# IRC2K16.net
KiCad netlist of a schematic drawn in EAGLE
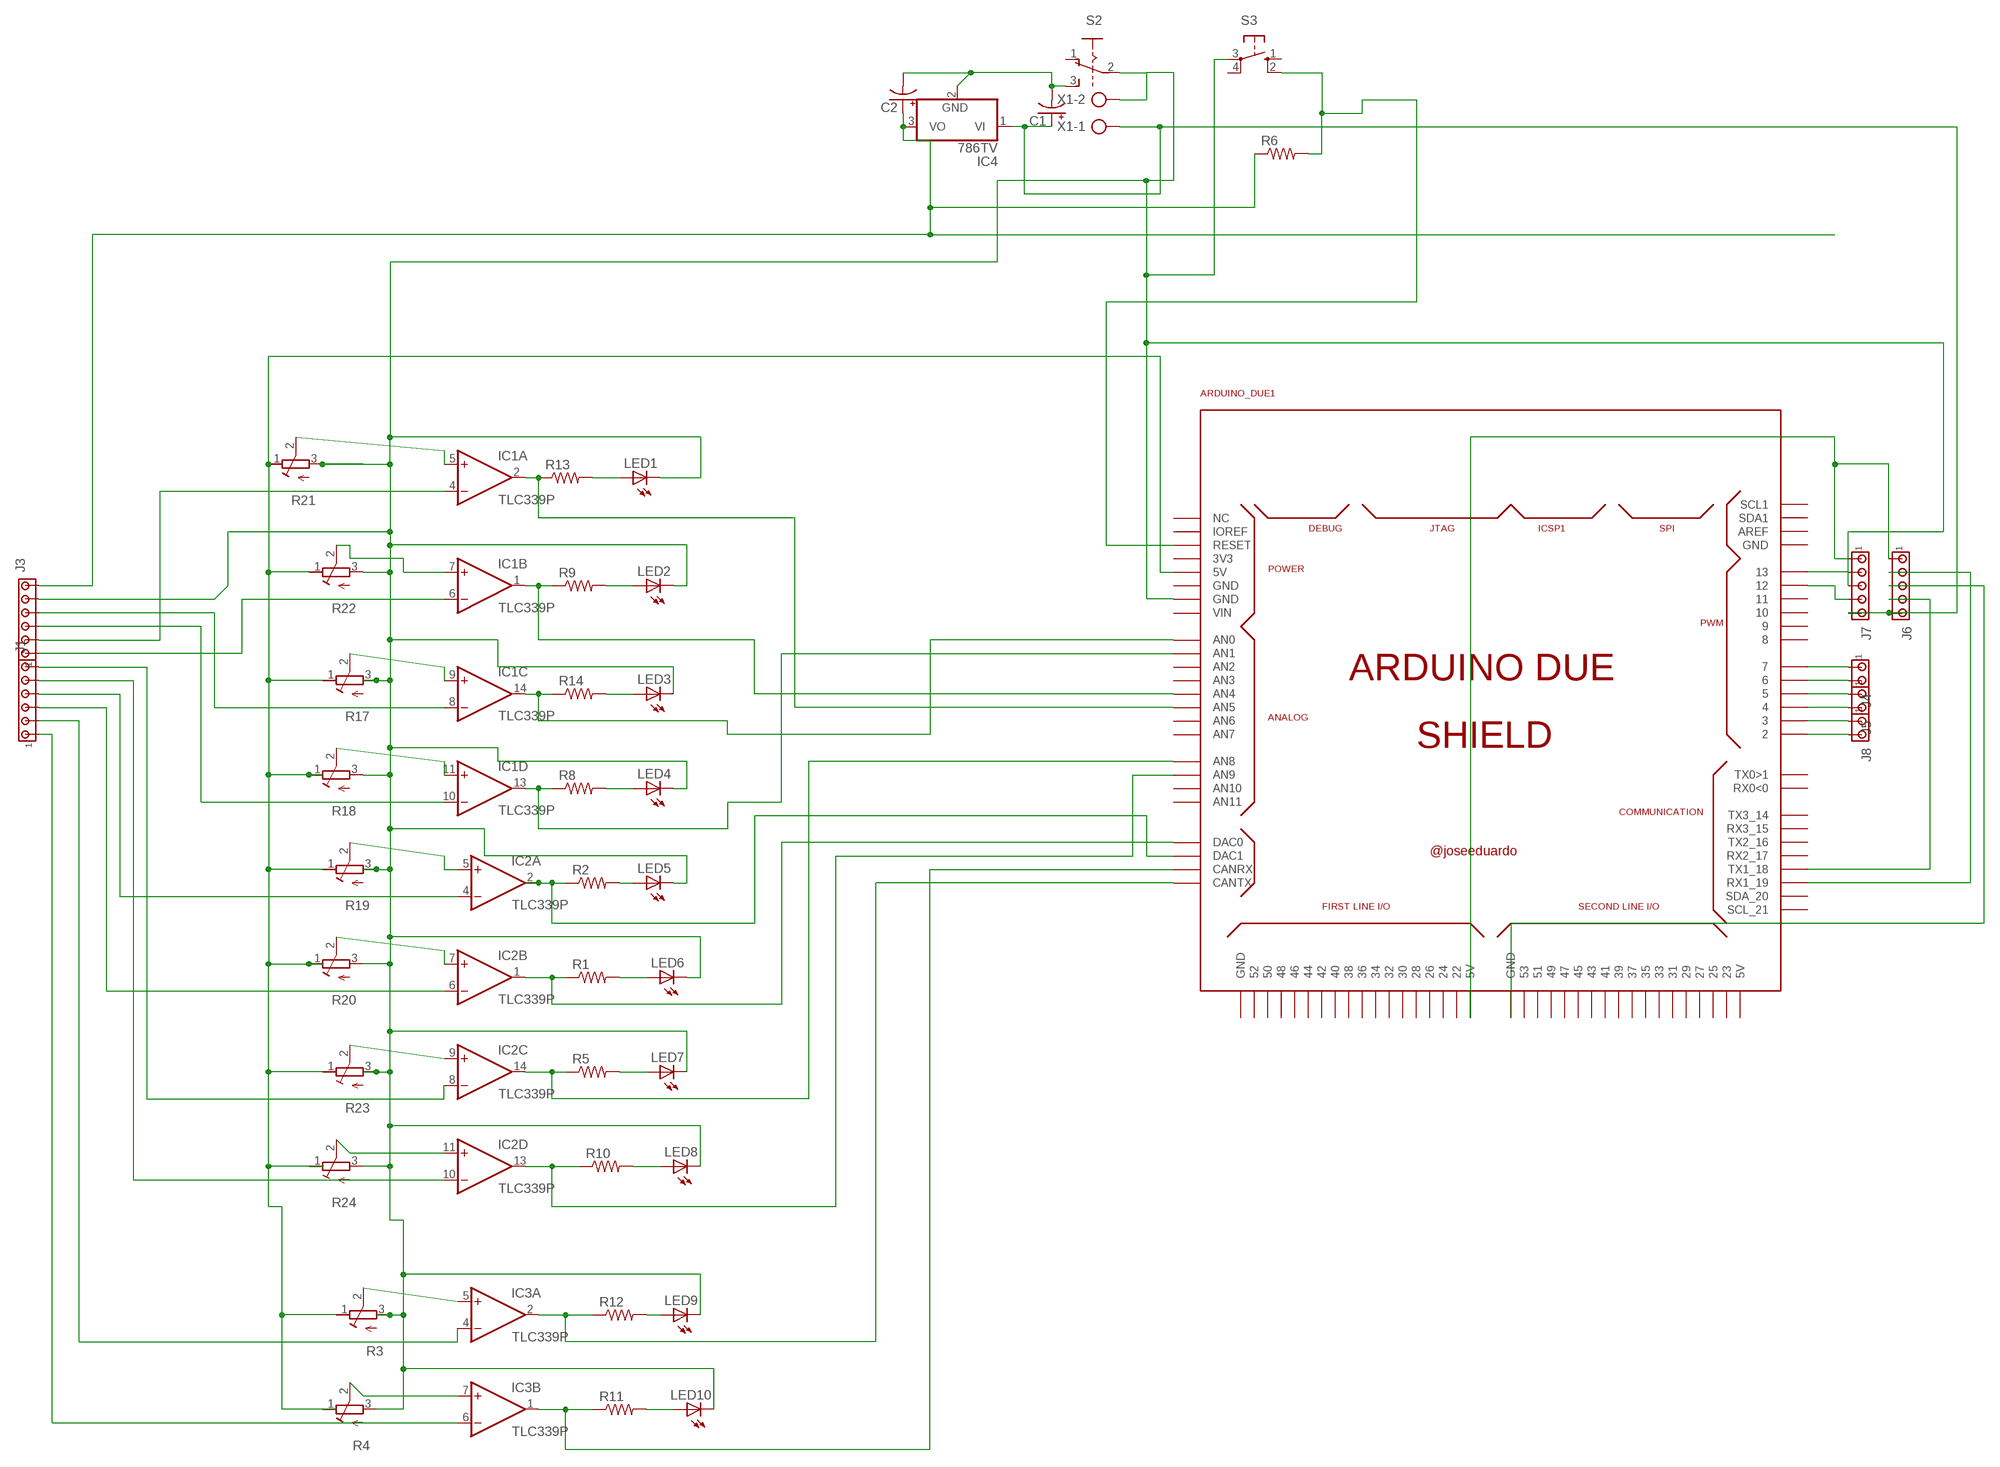
[diagram p0: schematic, sheet 1]
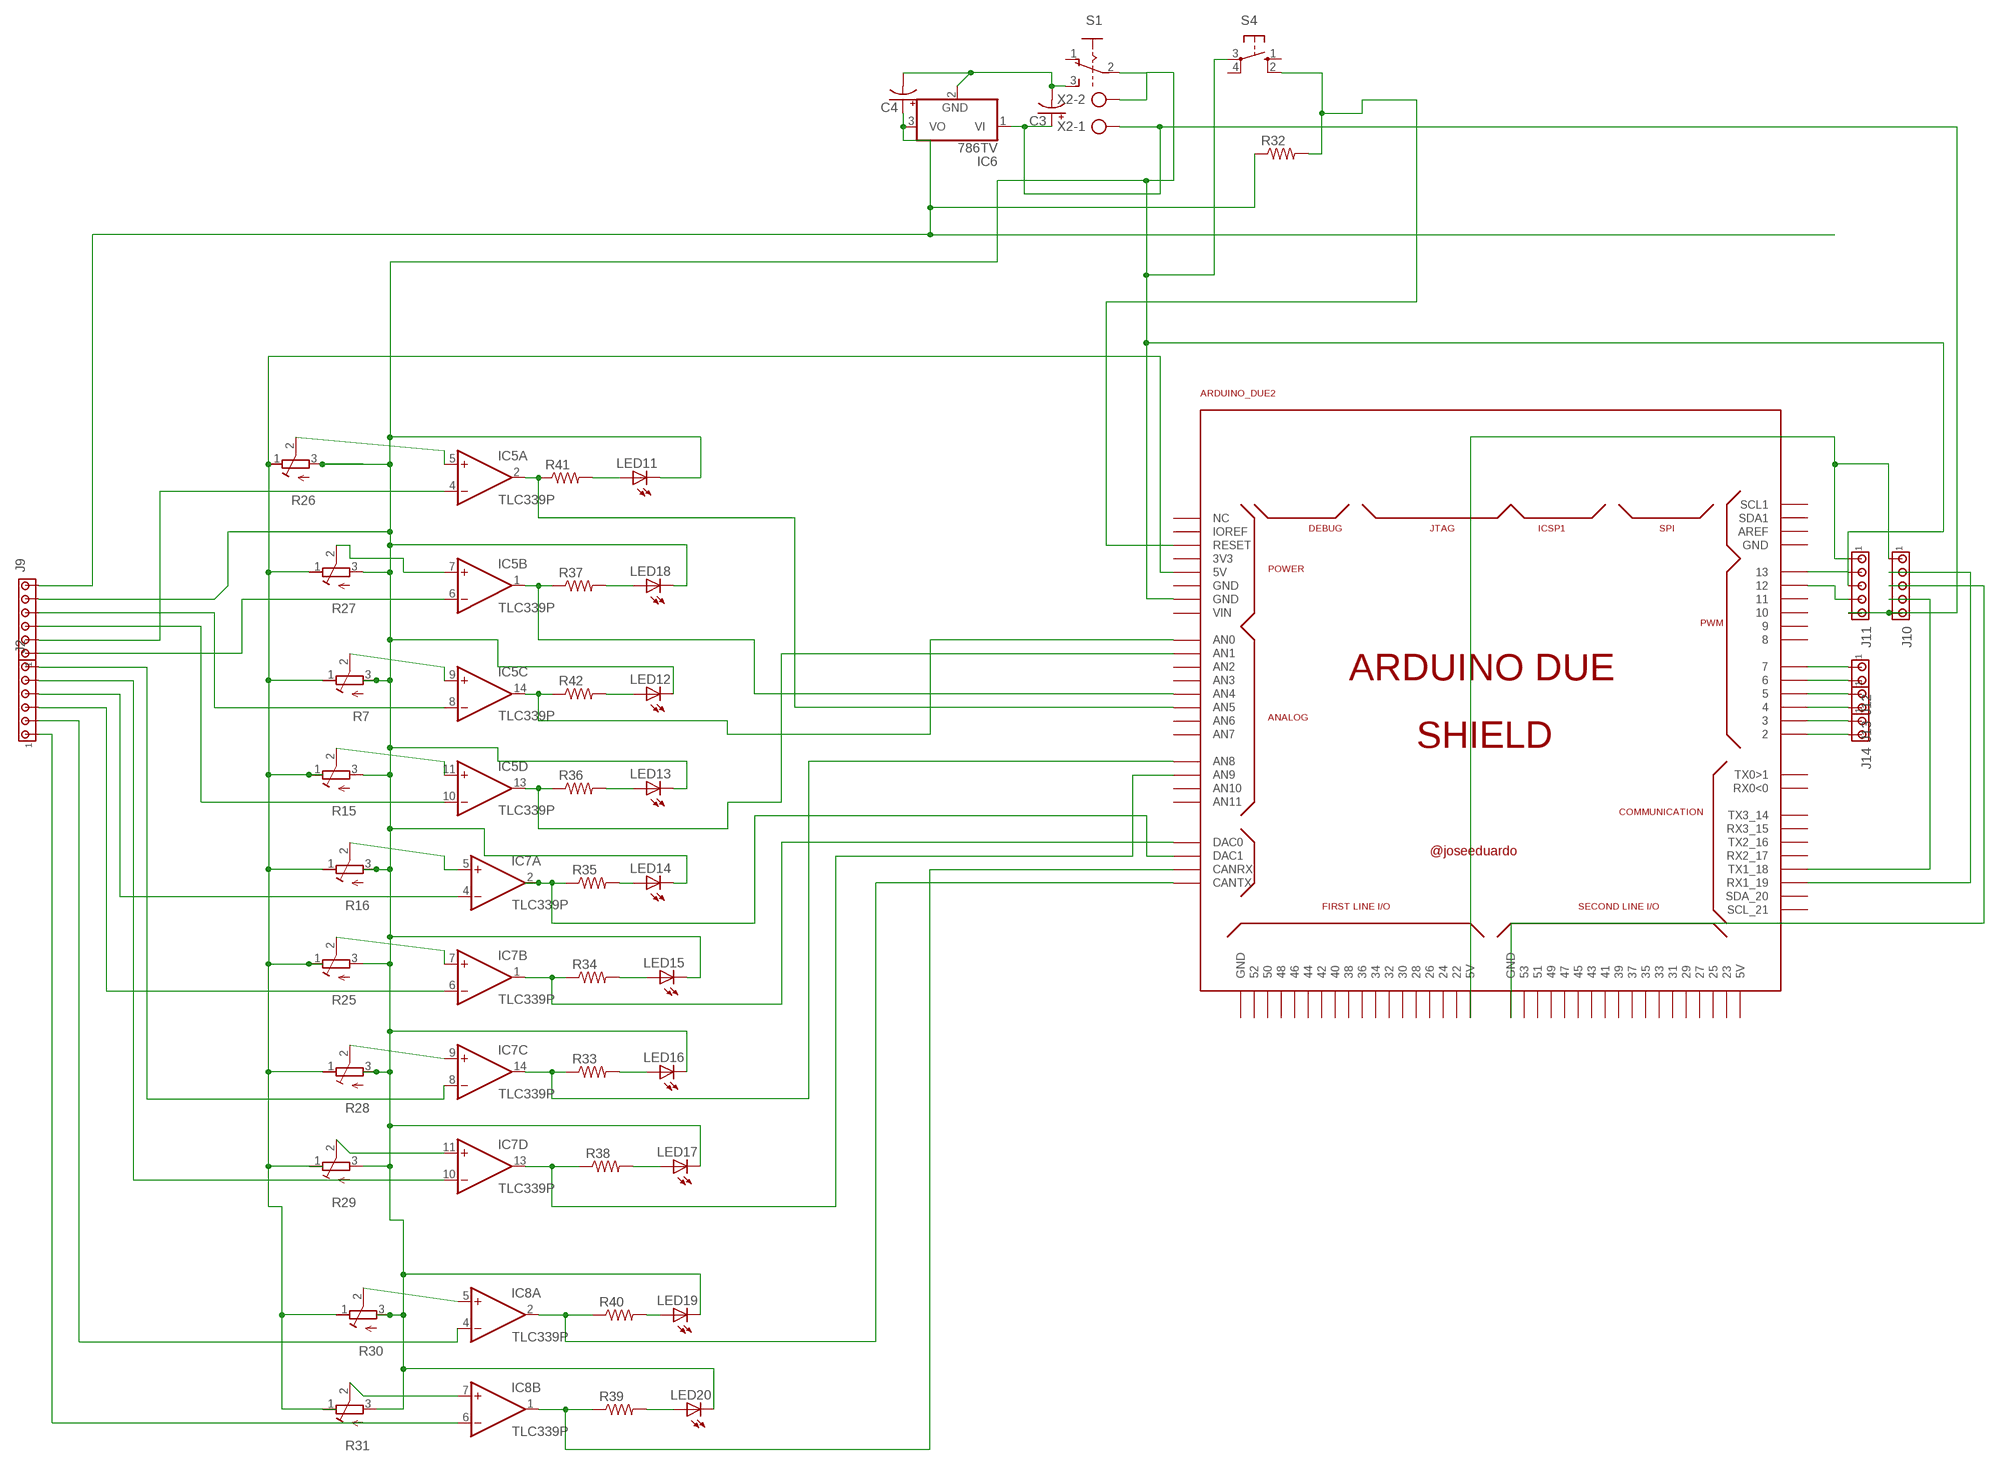
[diagram p1: schematic, sheet 2]

(export (version "E")
  (design (tool "Eeschema 10.0.6"))
  (components
    (comp (ref "ARDUINO_DUE1")
      (value "ARDUINO_DUE_SHIELD")
      (footprint "eagle-import:ARDUINO_DUE_SHIELD")
      (libsource (lib "eagle-import") (part "ARDUINO_DUE_SHIELD"))
    )
    (comp (ref "C1")
      (value "CPOL-USE5-10.5")
      (footprint "eagle-import:E5-10,5")
      (libsource (lib "eagle-import") (part "CPOL-USE5-10.5"))
    )
    (comp (ref "C2")
      (value "CPOL-USE5-10.5")
      (footprint "eagle-import:E5-10,5")
      (libsource (lib "eagle-import") (part "CPOL-USE5-10.5"))
    )
    (comp (ref "IC1")
      (value "TLC339P")
      (footprint "eagle-import:DIL14")
      (libsource (lib "eagle-import") (part "TLC339P"))
    )
    (comp (ref "IC2")
      (value "TLC339P")
      (footprint "eagle-import:DIL14")
      (libsource (lib "eagle-import") (part "TLC339P"))
    )
    (comp (ref "IC3")
      (value "TLC339P")
      (footprint "eagle-import:DIL14")
      (libsource (lib "eagle-import") (part "TLC339P"))
    )
    (comp (ref "IC4")
      (value "786TV")
      (footprint "eagle-import:TO220V")
      (libsource (lib "eagle-import") (part "78TV6"))
    )
    (comp (ref "J1")
      (value "MTA06-100")
      (footprint "eagle-import:10X06MTA")
      (libsource (lib "eagle-import") (part "MTA06-100"))
    )
    (comp (ref "J3")
      (value "MTA06-100")
      (footprint "eagle-import:10X06MTA")
      (libsource (lib "eagle-import") (part "MTA06-100"))
    )
    (comp (ref "J4")
      (value "MTA02-100")
      (footprint "eagle-import:10X02MTA")
      (libsource (lib "eagle-import") (part "MTA02-100"))
    )
    (comp (ref "J5")
      (value "MTA02-100")
      (footprint "eagle-import:10X02MTA")
      (libsource (lib "eagle-import") (part "MTA02-100"))
    )
    (comp (ref "J6")
      (value "MTA05-100")
      (footprint "eagle-import:10X05MTA")
      (libsource (lib "eagle-import") (part "MTA05-100"))
    )
    (comp (ref "J7")
      (value "MTA05-100")
      (footprint "eagle-import:10X05MTA")
      (libsource (lib "eagle-import") (part "MTA05-100"))
    )
    (comp (ref "J8")
      (value "MTA02-100")
      (footprint "eagle-import:10X02MTA")
      (libsource (lib "eagle-import") (part "MTA02-100"))
    )
    (comp (ref "LED1")
      (value "LED3MM")
      (footprint "eagle-import:LED3MM")
      (libsource (lib "eagle-import") (part "LED3MM"))
    )
    (comp (ref "LED2")
      (value "LED3MM")
      (footprint "eagle-import:LED3MM")
      (libsource (lib "eagle-import") (part "LED3MM"))
    )
    (comp (ref "LED3")
      (value "LED3MM")
      (footprint "eagle-import:LED3MM")
      (libsource (lib "eagle-import") (part "LED3MM"))
    )
    (comp (ref "LED4")
      (value "LED3MM")
      (footprint "eagle-import:LED3MM")
      (libsource (lib "eagle-import") (part "LED3MM"))
    )
    (comp (ref "LED5")
      (value "LED3MM")
      (footprint "eagle-import:LED3MM")
      (libsource (lib "eagle-import") (part "LED3MM"))
    )
    (comp (ref "LED6")
      (value "LED3MM")
      (footprint "eagle-import:LED3MM")
      (libsource (lib "eagle-import") (part "LED3MM"))
    )
    (comp (ref "LED7")
      (value "LED3MM")
      (footprint "eagle-import:LED3MM")
      (libsource (lib "eagle-import") (part "LED3MM"))
    )
    (comp (ref "LED8")
      (value "LED3MM")
      (footprint "eagle-import:LED3MM")
      (libsource (lib "eagle-import") (part "LED3MM"))
    )
    (comp (ref "LED9")
      (value "LED3MM")
      (footprint "eagle-import:LED3MM")
      (libsource (lib "eagle-import") (part "LED3MM"))
    )
    (comp (ref "LED10")
      (value "LED3MM")
      (footprint "eagle-import:LED3MM")
      (libsource (lib "eagle-import") (part "LED3MM"))
    )
    (comp (ref "R1")
      (value "R-US_0411/3V")
      (footprint "eagle-import:0411V")
      (libsource (lib "eagle-import") (part "resistor_R-US_0411/3V"))
    )
    (comp (ref "R2")
      (value "R-US_0411/3V")
      (footprint "eagle-import:0411V")
      (libsource (lib "eagle-import") (part "resistor_R-US_0411/3V"))
    )
    (comp (ref "R3")
      (value "R-TRIMMT93YA")
      (footprint "eagle-import:RTRIMT93YA")
      (libsource (lib "eagle-import") (part "R-TRIMMT93YA"))
    )
    (comp (ref "R4")
      (value "R-TRIMMT93YA")
      (footprint "eagle-import:RTRIMT93YA")
      (libsource (lib "eagle-import") (part "R-TRIMMT93YA"))
    )
    (comp (ref "R5")
      (value "R-US_0411/3V")
      (footprint "eagle-import:0411V")
      (libsource (lib "eagle-import") (part "resistor_R-US_0411/3V"))
    )
    (comp (ref "R6")
      (value "R-US_0207/10")
      (footprint "eagle-import:0207_10")
      (libsource (lib "eagle-import") (part "R-US_0207/10"))
    )
    (comp (ref "R8")
      (value "R-US_0411/3V")
      (footprint "eagle-import:0411V")
      (libsource (lib "eagle-import") (part "resistor_R-US_0411/3V"))
    )
    (comp (ref "R9")
      (value "R-US_0411/3V")
      (footprint "eagle-import:0411V")
      (libsource (lib "eagle-import") (part "resistor_R-US_0411/3V"))
    )
    (comp (ref "R10")
      (value "R-US_0411/3V")
      (footprint "eagle-import:0411V")
      (libsource (lib "eagle-import") (part "resistor_R-US_0411/3V"))
    )
    (comp (ref "R11")
      (value "R-US_0411/3V")
      (footprint "eagle-import:0411V")
      (libsource (lib "eagle-import") (part "resistor_R-US_0411/3V"))
    )
    (comp (ref "R12")
      (value "R-US_0411/3V")
      (footprint "eagle-import:0411V")
      (libsource (lib "eagle-import") (part "resistor_R-US_0411/3V"))
    )
    (comp (ref "R13")
      (value "R-US_0411/3V")
      (footprint "eagle-import:0411V")
      (libsource (lib "eagle-import") (part "resistor_R-US_0411/3V"))
    )
    (comp (ref "R14")
      (value "R-US_0411/3V")
      (footprint "eagle-import:0411V")
      (libsource (lib "eagle-import") (part "resistor_R-US_0411/3V"))
    )
    (comp (ref "R17")
      (value "R-TRIMMT93YA")
      (footprint "eagle-import:RTRIMT93YA")
      (libsource (lib "eagle-import") (part "R-TRIMMT93YA"))
    )
    (comp (ref "R18")
      (value "R-TRIMMT93YA")
      (footprint "eagle-import:RTRIMT93YA")
      (libsource (lib "eagle-import") (part "R-TRIMMT93YA"))
    )
    (comp (ref "R19")
      (value "R-TRIMMT93YA")
      (footprint "eagle-import:RTRIMT93YA")
      (libsource (lib "eagle-import") (part "R-TRIMMT93YA"))
    )
    (comp (ref "R20")
      (value "R-TRIMMT93YA")
      (footprint "eagle-import:RTRIMT93YA")
      (libsource (lib "eagle-import") (part "R-TRIMMT93YA"))
    )
    (comp (ref "R21")
      (value "R-TRIMMT93YA")
      (footprint "eagle-import:RTRIMT93YA")
      (libsource (lib "eagle-import") (part "R-TRIMMT93YA"))
    )
    (comp (ref "R22")
      (value "R-TRIMMT93YA")
      (footprint "eagle-import:RTRIMT93YA")
      (libsource (lib "eagle-import") (part "R-TRIMMT93YA"))
    )
    (comp (ref "R23")
      (value "R-TRIMMT93YA")
      (footprint "eagle-import:RTRIMT93YA")
      (libsource (lib "eagle-import") (part "R-TRIMMT93YA"))
    )
    (comp (ref "R24")
      (value "R-TRIMMT93YA")
      (footprint "eagle-import:RTRIMT93YA")
      (libsource (lib "eagle-import") (part "R-TRIMMT93YA"))
    )
    (comp (ref "S2")
      (value "A68-A31")
      (footprint "eagle-import:A68-A31")
      (libsource (lib "eagle-import") (part "A68-A31"))
    )
    (comp (ref "S3")
      (value "10-XX")
      (footprint "eagle-import:B3F-10XX")
      (fields (field (name "MPN") "B3F-1000"))
      (libsource (lib "eagle-import") (part "10-XX"))
    )
    (comp (ref "X1")
      (value "AK300/2")
      (footprint "eagle-import:AK300_2")
      (libsource (lib "eagle-import") (part "AK300/2"))
    )
    (comp (ref "ARDUINO_DUE2")
      (value "ARDUINO_DUE_SHIELD")
      (footprint "eagle-import:ARDUINO_DUE_SHIELD")
      (libsource (lib "eagle-import") (part "ARDUINO_DUE_SHIELD"))
    )
    (comp (ref "C3")
      (value "CPOL-USE5-10.5")
      (footprint "eagle-import:E5-10,5")
      (libsource (lib "eagle-import") (part "CPOL-USE5-10.5"))
    )
    (comp (ref "C4")
      (value "CPOL-USE5-10.5")
      (footprint "eagle-import:E5-10,5")
      (libsource (lib "eagle-import") (part "CPOL-USE5-10.5"))
    )
    (comp (ref "IC5")
      (value "TLC339P")
      (footprint "eagle-import:DIL14")
      (libsource (lib "eagle-import") (part "TLC339P"))
    )
    (comp (ref "IC6")
      (value "786TV")
      (footprint "eagle-import:TO220V")
      (libsource (lib "eagle-import") (part "78TV6"))
    )
    (comp (ref "IC7")
      (value "TLC339P")
      (footprint "eagle-import:DIL14")
      (libsource (lib "eagle-import") (part "TLC339P"))
    )
    (comp (ref "IC8")
      (value "TLC339P")
      (footprint "eagle-import:DIL14")
      (libsource (lib "eagle-import") (part "TLC339P"))
    )
    (comp (ref "J2")
      (value "MTA06-100")
      (footprint "eagle-import:10X06MTA")
      (libsource (lib "eagle-import") (part "MTA06-100"))
    )
    (comp (ref "J9")
      (value "MTA06-100")
      (footprint "eagle-import:10X06MTA")
      (libsource (lib "eagle-import") (part "MTA06-100"))
    )
    (comp (ref "J10")
      (value "MTA05-100")
      (footprint "eagle-import:10X05MTA")
      (libsource (lib "eagle-import") (part "MTA05-100"))
    )
    (comp (ref "J11")
      (value "MTA05-100")
      (footprint "eagle-import:10X05MTA")
      (libsource (lib "eagle-import") (part "MTA05-100"))
    )
    (comp (ref "J12")
      (value "MTA02-100")
      (footprint "eagle-import:10X02MTA")
      (libsource (lib "eagle-import") (part "MTA02-100"))
    )
    (comp (ref "J13")
      (value "MTA02-100")
      (footprint "eagle-import:10X02MTA")
      (libsource (lib "eagle-import") (part "MTA02-100"))
    )
    (comp (ref "J14")
      (value "MTA02-100")
      (footprint "eagle-import:10X02MTA")
      (libsource (lib "eagle-import") (part "MTA02-100"))
    )
    (comp (ref "LED11")
      (value "LED3MM")
      (footprint "eagle-import:LED3MM")
      (libsource (lib "eagle-import") (part "LED3MM"))
    )
    (comp (ref "LED12")
      (value "LED3MM")
      (footprint "eagle-import:LED3MM")
      (libsource (lib "eagle-import") (part "LED3MM"))
    )
    (comp (ref "LED13")
      (value "LED3MM")
      (footprint "eagle-import:LED3MM")
      (libsource (lib "eagle-import") (part "LED3MM"))
    )
    (comp (ref "LED14")
      (value "LED3MM")
      (footprint "eagle-import:LED3MM")
      (libsource (lib "eagle-import") (part "LED3MM"))
    )
    (comp (ref "LED15")
      (value "LED3MM")
      (footprint "eagle-import:LED3MM")
      (libsource (lib "eagle-import") (part "LED3MM"))
    )
    (comp (ref "LED16")
      (value "LED3MM")
      (footprint "eagle-import:LED3MM")
      (libsource (lib "eagle-import") (part "LED3MM"))
    )
    (comp (ref "LED17")
      (value "LED3MM")
      (footprint "eagle-import:LED3MM")
      (libsource (lib "eagle-import") (part "LED3MM"))
    )
    (comp (ref "LED18")
      (value "LED3MM")
      (footprint "eagle-import:LED3MM")
      (libsource (lib "eagle-import") (part "LED3MM"))
    )
    (comp (ref "LED19")
      (value "LED3MM")
      (footprint "eagle-import:LED3MM")
      (libsource (lib "eagle-import") (part "LED3MM"))
    )
    (comp (ref "LED20")
      (value "LED3MM")
      (footprint "eagle-import:LED3MM")
      (libsource (lib "eagle-import") (part "LED3MM"))
    )
    (comp (ref "R7")
      (value "R-TRIMMT93YA")
      (footprint "eagle-import:RTRIMT93YA")
      (libsource (lib "eagle-import") (part "R-TRIMMT93YA"))
    )
    (comp (ref "R15")
      (value "R-TRIMMT93YA")
      (footprint "eagle-import:RTRIMT93YA")
      (libsource (lib "eagle-import") (part "R-TRIMMT93YA"))
    )
    (comp (ref "R16")
      (value "R-TRIMMT93YA")
      (footprint "eagle-import:RTRIMT93YA")
      (libsource (lib "eagle-import") (part "R-TRIMMT93YA"))
    )
    (comp (ref "R25")
      (value "R-TRIMMT93YA")
      (footprint "eagle-import:RTRIMT93YA")
      (libsource (lib "eagle-import") (part "R-TRIMMT93YA"))
    )
    (comp (ref "R26")
      (value "R-TRIMMT93YA")
      (footprint "eagle-import:RTRIMT93YA")
      (libsource (lib "eagle-import") (part "R-TRIMMT93YA"))
    )
    (comp (ref "R27")
      (value "R-TRIMMT93YA")
      (footprint "eagle-import:RTRIMT93YA")
      (libsource (lib "eagle-import") (part "R-TRIMMT93YA"))
    )
    (comp (ref "R28")
      (value "R-TRIMMT93YA")
      (footprint "eagle-import:RTRIMT93YA")
      (libsource (lib "eagle-import") (part "R-TRIMMT93YA"))
    )
    (comp (ref "R29")
      (value "R-TRIMMT93YA")
      (footprint "eagle-import:RTRIMT93YA")
      (libsource (lib "eagle-import") (part "R-TRIMMT93YA"))
    )
    (comp (ref "R30")
      (value "R-TRIMMT93YA")
      (footprint "eagle-import:RTRIMT93YA")
      (libsource (lib "eagle-import") (part "R-TRIMMT93YA"))
    )
    (comp (ref "R31")
      (value "R-TRIMMT93YA")
      (footprint "eagle-import:RTRIMT93YA")
      (libsource (lib "eagle-import") (part "R-TRIMMT93YA"))
    )
    (comp (ref "R32")
      (value "R-US_0207/10")
      (footprint "eagle-import:0207_10")
      (libsource (lib "eagle-import") (part "R-US_0207/10"))
    )
    (comp (ref "R33")
      (value "R-US_0411/3V")
      (footprint "eagle-import:0411V")
      (libsource (lib "eagle-import") (part "resistor_R-US_0411/3V"))
    )
    (comp (ref "R34")
      (value "R-US_0411/3V")
      (footprint "eagle-import:0411V")
      (libsource (lib "eagle-import") (part "resistor_R-US_0411/3V"))
    )
    (comp (ref "R35")
      (value "R-US_0411/3V")
      (footprint "eagle-import:0411V")
      (libsource (lib "eagle-import") (part "resistor_R-US_0411/3V"))
    )
    (comp (ref "R36")
      (value "R-US_0411/3V")
      (footprint "eagle-import:0411V")
      (libsource (lib "eagle-import") (part "resistor_R-US_0411/3V"))
    )
    (comp (ref "R37")
      (value "R-US_0411/3V")
      (footprint "eagle-import:0411V")
      (libsource (lib "eagle-import") (part "resistor_R-US_0411/3V"))
    )
    (comp (ref "R38")
      (value "R-US_0411/3V")
      (footprint "eagle-import:0411V")
      (libsource (lib "eagle-import") (part "resistor_R-US_0411/3V"))
    )
    (comp (ref "R39")
      (value "R-US_0411/3V")
      (footprint "eagle-import:0411V")
      (libsource (lib "eagle-import") (part "resistor_R-US_0411/3V"))
    )
    (comp (ref "R40")
      (value "R-US_0411/3V")
      (footprint "eagle-import:0411V")
      (libsource (lib "eagle-import") (part "resistor_R-US_0411/3V"))
    )
    (comp (ref "R41")
      (value "R-US_0411/3V")
      (footprint "eagle-import:0411V")
      (libsource (lib "eagle-import") (part "resistor_R-US_0411/3V"))
    )
    (comp (ref "R42")
      (value "R-US_0411/3V")
      (footprint "eagle-import:0411V")
      (libsource (lib "eagle-import") (part "resistor_R-US_0411/3V"))
    )
    (comp (ref "S1")
      (value "A68-A31")
      (footprint "eagle-import:A68-A31")
      (libsource (lib "eagle-import") (part "A68-A31"))
    )
    (comp (ref "S4")
      (value "10-XX")
      (footprint "eagle-import:B3F-10XX")
      (fields (field (name "MPN") "B3F-1000"))
      (libsource (lib "eagle-import") (part "10-XX"))
    )
    (comp (ref "X2")
      (value "AK300/2")
      (footprint "eagle-import:AK300_2")
      (libsource (lib "eagle-import") (part "AK300/2"))
    )
  )
  (nets
    (net (code "1") (name "Net-(ARDUINO_DUE1-5V-Pad5V0_1)") (class "Default")
      (node (ref "ARDUINO_DUE1") (pin "5V0_1") (pinfunction "5V_5V0_1") (pintype "bidirectional"))
      (node (ref "J6") (pin "1") (pinfunction "1_1") (pintype "passive"))
      (node (ref "J7") (pin "1") (pinfunction "1_1") (pintype "passive"))
    )
    (net (code "2") (name "Net-(ARDUINO_DUE1-AN0)") (class "Default")
      (node (ref "ARDUINO_DUE1") (pin "A0") (pinfunction "AN0_A0") (pintype "bidirectional"))
      (node (ref "IC1") (pin "14") (pinfunction "OUT_14") (pintype "output"))
      (node (ref "R14") (pin "1") (pinfunction "1_1") (pintype "passive"))
    )
    (net (code "3") (name "Net-(ARDUINO_DUE1-AN1)") (class "Default")
      (node (ref "ARDUINO_DUE1") (pin "A1") (pinfunction "AN1_A1") (pintype "bidirectional"))
      (node (ref "IC1") (pin "13") (pinfunction "OUT_13") (pintype "output"))
      (node (ref "R8") (pin "1") (pinfunction "1_1") (pintype "passive"))
    )
    (net (code "4") (name "Net-(ARDUINO_DUE1-AN4)") (class "Default")
      (node (ref "ARDUINO_DUE1") (pin "A4") (pinfunction "AN4_A4") (pintype "bidirectional"))
      (node (ref "IC1") (pin "1") (pinfunction "OUT_1") (pintype "output"))
      (node (ref "R9") (pin "1") (pinfunction "1_1") (pintype "passive"))
    )
    (net (code "5") (name "Net-(ARDUINO_DUE1-AN5)") (class "Default")
      (node (ref "ARDUINO_DUE1") (pin "A5") (pinfunction "AN5_A5") (pintype "bidirectional"))
      (node (ref "IC1") (pin "2") (pinfunction "OUT_2") (pintype "output"))
      (node (ref "R13") (pin "1") (pinfunction "1_1") (pintype "passive"))
    )
    (net (code "6") (name "Net-(ARDUINO_DUE1-AN8)") (class "Default")
      (node (ref "ARDUINO_DUE1") (pin "A8") (pinfunction "AN8_A8") (pintype "bidirectional"))
      (node (ref "IC2") (pin "14") (pinfunction "OUT_14") (pintype "output"))
      (node (ref "R5") (pin "1") (pinfunction "1_1") (pintype "passive"))
    )
    (net (code "7") (name "Net-(ARDUINO_DUE1-AN9)") (class "Default")
      (node (ref "ARDUINO_DUE1") (pin "A9") (pinfunction "AN9_A9") (pintype "bidirectional"))
      (node (ref "IC2") (pin "13") (pinfunction "OUT_13") (pintype "output"))
      (node (ref "R10") (pin "1") (pinfunction "1_1") (pintype "passive"))
    )
    (net (code "8") (name "Net-(ARDUINO_DUE1-GND-PadGND_3)") (class "Default")
      (node (ref "ARDUINO_DUE1") (pin "GND_3") (pinfunction "GND_GND_3") (pintype "bidirectional"))
      (node (ref "J6") (pin "3") (pinfunction "3_3") (pintype "passive"))
    )
    (net (code "9") (name "Net-(ARDUINO_DUE1-Pad2)") (class "Default")
      (node (ref "ARDUINO_DUE1") (pin "2") (pinfunction "2_2") (pintype "bidirectional"))
      (node (ref "J8") (pin "2") (pinfunction "2_2") (pintype "passive"))
    )
    (net (code "10") (name "Net-(ARDUINO_DUE1-Pad3)") (class "Default")
      (node (ref "ARDUINO_DUE1") (pin "3") (pinfunction "3_3") (pintype "bidirectional"))
      (node (ref "J8") (pin "1") (pinfunction "1_1") (pintype "passive"))
    )
    (net (code "11") (name "Net-(ARDUINO_DUE1-Pad4)") (class "Default")
      (node (ref "ARDUINO_DUE1") (pin "4") (pinfunction "4_4") (pintype "bidirectional"))
      (node (ref "J5") (pin "2") (pinfunction "2_2") (pintype "passive"))
    )
    (net (code "12") (name "Net-(ARDUINO_DUE1-Pad5)") (class "Default")
      (node (ref "ARDUINO_DUE1") (pin "5") (pinfunction "5_5") (pintype "bidirectional"))
      (node (ref "J5") (pin "1") (pinfunction "1_1") (pintype "passive"))
    )
    (net (code "13") (name "Net-(ARDUINO_DUE1-Pad6)") (class "Default")
      (node (ref "ARDUINO_DUE1") (pin "6") (pinfunction "6_6") (pintype "bidirectional"))
      (node (ref "J4") (pin "2") (pinfunction "2_2") (pintype "passive"))
    )
    (net (code "14") (name "Net-(ARDUINO_DUE1-Pad7)") (class "Default")
      (node (ref "ARDUINO_DUE1") (pin "7") (pinfunction "7_7") (pintype "bidirectional"))
      (node (ref "J4") (pin "1") (pinfunction "1_1") (pintype "passive"))
    )
    (net (code "15") (name "Net-(ARDUINO_DUE1-Pad12)") (class "Default")
      (node (ref "ARDUINO_DUE1") (pin "12") (pinfunction "12_12") (pintype "bidirectional"))
      (node (ref "J7") (pin "4") (pinfunction "4_4") (pintype "passive"))
    )
    (net (code "16") (name "Net-(ARDUINO_DUE1-Pad13)") (class "Default")
      (node (ref "ARDUINO_DUE1") (pin "13") (pinfunction "13_13") (pintype "bidirectional"))
      (node (ref "J7") (pin "2") (pinfunction "2_2") (pintype "passive"))
    )
    (net (code "17") (name "Net-(ARDUINO_DUE1-RX1_19)") (class "Default")
      (node (ref "ARDUINO_DUE1") (pin "19") (pinfunction "RX1_19_19") (pintype "bidirectional"))
      (node (ref "J6") (pin "2") (pinfunction "2_2") (pintype "passive"))
    )
    (net (code "18") (name "Net-(ARDUINO_DUE1-TX1_18)") (class "Default")
      (node (ref "ARDUINO_DUE1") (pin "18") (pinfunction "TX1_18_18") (pintype "bidirectional"))
      (node (ref "J6") (pin "4") (pinfunction "4_4") (pintype "passive"))
    )
    (net (code "19") (name "Net-(ARDUINO_DUE2-5V-Pad5V0_1)") (class "Default")
      (node (ref "ARDUINO_DUE2") (pin "5V0_1") (pinfunction "5V_5V0_1") (pintype "bidirectional"))
      (node (ref "J10") (pin "1") (pinfunction "1_1") (pintype "passive"))
      (node (ref "J11") (pin "1") (pinfunction "1_1") (pintype "passive"))
    )
    (net (code "20") (name "Net-(ARDUINO_DUE2-AN0)") (class "Default")
      (node (ref "ARDUINO_DUE2") (pin "A0") (pinfunction "AN0_A0") (pintype "bidirectional"))
      (node (ref "IC5") (pin "14") (pinfunction "OUT_14") (pintype "output"))
      (node (ref "R42") (pin "1") (pinfunction "1_1") (pintype "passive"))
    )
    (net (code "21") (name "Net-(ARDUINO_DUE2-AN1)") (class "Default")
      (node (ref "ARDUINO_DUE2") (pin "A1") (pinfunction "AN1_A1") (pintype "bidirectional"))
      (node (ref "IC5") (pin "13") (pinfunction "OUT_13") (pintype "output"))
      (node (ref "R36") (pin "1") (pinfunction "1_1") (pintype "passive"))
    )
    (net (code "22") (name "Net-(ARDUINO_DUE2-AN4)") (class "Default")
      (node (ref "ARDUINO_DUE2") (pin "A4") (pinfunction "AN4_A4") (pintype "bidirectional"))
      (node (ref "IC5") (pin "1") (pinfunction "OUT_1") (pintype "output"))
      (node (ref "R37") (pin "1") (pinfunction "1_1") (pintype "passive"))
    )
    (net (code "23") (name "Net-(ARDUINO_DUE2-AN5)") (class "Default")
      (node (ref "ARDUINO_DUE2") (pin "A5") (pinfunction "AN5_A5") (pintype "bidirectional"))
      (node (ref "IC5") (pin "2") (pinfunction "OUT_2") (pintype "output"))
      (node (ref "R41") (pin "1") (pinfunction "1_1") (pintype "passive"))
    )
    (net (code "24") (name "Net-(ARDUINO_DUE2-AN8)") (class "Default")
      (node (ref "ARDUINO_DUE2") (pin "A8") (pinfunction "AN8_A8") (pintype "bidirectional"))
      (node (ref "IC7") (pin "14") (pinfunction "OUT_14") (pintype "output"))
      (node (ref "R33") (pin "1") (pinfunction "1_1") (pintype "passive"))
    )
    (net (code "25") (name "Net-(ARDUINO_DUE2-AN9)") (class "Default")
      (node (ref "ARDUINO_DUE2") (pin "A9") (pinfunction "AN9_A9") (pintype "bidirectional"))
      (node (ref "IC7") (pin "13") (pinfunction "OUT_13") (pintype "output"))
      (node (ref "R38") (pin "1") (pinfunction "1_1") (pintype "passive"))
    )
    (net (code "26") (name "Net-(ARDUINO_DUE2-GND-PadGND_3)") (class "Default")
      (node (ref "ARDUINO_DUE2") (pin "GND_3") (pinfunction "GND_GND_3") (pintype "bidirectional"))
      (node (ref "J10") (pin "3") (pinfunction "3_3") (pintype "passive"))
    )
    (net (code "27") (name "Net-(ARDUINO_DUE2-Pad2)") (class "Default")
      (node (ref "ARDUINO_DUE2") (pin "2") (pinfunction "2_2") (pintype "bidirectional"))
      (node (ref "J14") (pin "2") (pinfunction "2_2") (pintype "passive"))
    )
    (net (code "28") (name "Net-(ARDUINO_DUE2-Pad3)") (class "Default")
      (node (ref "ARDUINO_DUE2") (pin "3") (pinfunction "3_3") (pintype "bidirectional"))
      (node (ref "J14") (pin "1") (pinfunction "1_1") (pintype "passive"))
    )
    (net (code "29") (name "Net-(ARDUINO_DUE2-Pad4)") (class "Default")
      (node (ref "ARDUINO_DUE2") (pin "4") (pinfunction "4_4") (pintype "bidirectional"))
      (node (ref "J13") (pin "2") (pinfunction "2_2") (pintype "passive"))
    )
    (net (code "30") (name "Net-(ARDUINO_DUE2-Pad5)") (class "Default")
      (node (ref "ARDUINO_DUE2") (pin "5") (pinfunction "5_5") (pintype "bidirectional"))
      (node (ref "J13") (pin "1") (pinfunction "1_1") (pintype "passive"))
    )
    (net (code "31") (name "Net-(ARDUINO_DUE2-Pad6)") (class "Default")
      (node (ref "ARDUINO_DUE2") (pin "6") (pinfunction "6_6") (pintype "bidirectional"))
      (node (ref "J12") (pin "2") (pinfunction "2_2") (pintype "passive"))
    )
    (net (code "32") (name "Net-(ARDUINO_DUE2-Pad7)") (class "Default")
      (node (ref "ARDUINO_DUE2") (pin "7") (pinfunction "7_7") (pintype "bidirectional"))
      (node (ref "J12") (pin "1") (pinfunction "1_1") (pintype "passive"))
    )
    (net (code "33") (name "Net-(ARDUINO_DUE2-Pad12)") (class "Default")
      (node (ref "ARDUINO_DUE2") (pin "12") (pinfunction "12_12") (pintype "bidirectional"))
      (node (ref "J11") (pin "4") (pinfunction "4_4") (pintype "passive"))
    )
    (net (code "34") (name "Net-(ARDUINO_DUE2-Pad13)") (class "Default")
      (node (ref "ARDUINO_DUE2") (pin "13") (pinfunction "13_13") (pintype "bidirectional"))
      (node (ref "J11") (pin "2") (pinfunction "2_2") (pintype "passive"))
    )
    (net (code "35") (name "Net-(ARDUINO_DUE2-RX1_19)") (class "Default")
      (node (ref "ARDUINO_DUE2") (pin "19") (pinfunction "RX1_19_19") (pintype "bidirectional"))
      (node (ref "J10") (pin "2") (pinfunction "2_2") (pintype "passive"))
    )
    (net (code "36") (name "Net-(ARDUINO_DUE2-TX1_18)") (class "Default")
      (node (ref "ARDUINO_DUE2") (pin "18") (pinfunction "TX1_18_18") (pintype "bidirectional"))
      (node (ref "J10") (pin "4") (pinfunction "4_4") (pintype "passive"))
    )
    (net (code "37") (name "Net-(IC1A-+IN)") (class "Default")
      (node (ref "IC1") (pin "5") (pinfunction "+IN_5") (pintype "input"))
      (node (ref "R21") (pin "2") (pinfunction "S_2") (pintype "passive"))
    )
    (net (code "38") (name "Net-(IC1A--IN)") (class "Default")
      (node (ref "IC1") (pin "4") (pinfunction "-IN_4") (pintype "input"))
      (node (ref "J3") (pin "5") (pinfunction "2_5") (pintype "passive"))
    )
    (net (code "39") (name "Net-(IC1B-+IN)") (class "Default")
      (node (ref "IC1") (pin "7") (pinfunction "+IN_7") (pintype "input"))
      (node (ref "R22") (pin "2") (pinfunction "S_2") (pintype "passive"))
    )
    (net (code "40") (name "Net-(IC1B--IN)") (class "Default")
      (node (ref "IC1") (pin "6") (pinfunction "-IN_6") (pintype "input"))
      (node (ref "J3") (pin "6") (pinfunction "1_6") (pintype "passive"))
    )
    (net (code "41") (name "Net-(IC1C-+IN)") (class "Default")
      (node (ref "IC1") (pin "9") (pinfunction "+IN_9") (pintype "input"))
      (node (ref "R17") (pin "2") (pinfunction "S_2") (pintype "passive"))
    )
    (net (code "42") (name "Net-(IC1C--IN)") (class "Default")
      (node (ref "IC1") (pin "8") (pinfunction "-IN_8") (pintype "input"))
      (node (ref "J3") (pin "3") (pinfunction "4_3") (pintype "passive"))
    )
    (net (code "43") (name "Net-(IC1D-+IN)") (class "Default")
      (node (ref "IC1") (pin "11") (pinfunction "+IN_11") (pintype "input"))
      (node (ref "R18") (pin "2") (pinfunction "S_2") (pintype "passive"))
    )
    (net (code "44") (name "Net-(IC1D--IN)") (class "Default")
      (node (ref "IC1") (pin "10") (pinfunction "-IN_10") (pintype "input"))
      (node (ref "J3") (pin "4") (pinfunction "3_4") (pintype "passive"))
    )
    (net (code "45") (name "Net-(IC2A-+IN)") (class "Default")
      (node (ref "IC2") (pin "5") (pinfunction "+IN_5") (pintype "input"))
      (node (ref "R19") (pin "2") (pinfunction "S_2") (pintype "passive"))
    )
    (net (code "46") (name "Net-(IC2A--IN)") (class "Default")
      (node (ref "IC2") (pin "4") (pinfunction "-IN_4") (pintype "input"))
      (node (ref "J1") (pin "3") (pinfunction "4_3") (pintype "passive"))
    )
    (net (code "47") (name "Net-(IC2A-OUT)") (class "Default")
      (node (ref "ARDUINO_DUE1") (pin "DAC1") (pinfunction "DAC1_DAC1") (pintype "bidirectional"))
      (node (ref "IC2") (pin "2") (pinfunction "OUT_2") (pintype "output"))
      (node (ref "R2") (pin "1") (pinfunction "1_1") (pintype "passive"))
    )
    (net (code "48") (name "Net-(IC2B-+IN)") (class "Default")
      (node (ref "IC2") (pin "7") (pinfunction "+IN_7") (pintype "input"))
      (node (ref "R20") (pin "2") (pinfunction "S_2") (pintype "passive"))
    )
    (net (code "49") (name "Net-(IC2B--IN)") (class "Default")
      (node (ref "IC2") (pin "6") (pinfunction "-IN_6") (pintype "input"))
      (node (ref "J1") (pin "4") (pinfunction "3_4") (pintype "passive"))
    )
    (net (code "50") (name "Net-(IC2B-OUT)") (class "Default")
      (node (ref "ARDUINO_DUE1") (pin "DAC0") (pinfunction "DAC0_DAC0") (pintype "bidirectional"))
      (node (ref "IC2") (pin "1") (pinfunction "OUT_1") (pintype "output"))
      (node (ref "R1") (pin "1") (pinfunction "1_1") (pintype "passive"))
    )
    (net (code "51") (name "Net-(IC2C-+IN)") (class "Default")
      (node (ref "IC2") (pin "9") (pinfunction "+IN_9") (pintype "input"))
      (node (ref "R23") (pin "2") (pinfunction "S_2") (pintype "passive"))
    )
    (net (code "52") (name "Net-(IC2C--IN)") (class "Default")
      (node (ref "IC2") (pin "8") (pinfunction "-IN_8") (pintype "input"))
      (node (ref "J1") (pin "1") (pinfunction "6_1") (pintype "passive"))
    )
    (net (code "53") (name "Net-(IC2D-+IN)") (class "Default")
      (node (ref "IC2") (pin "11") (pinfunction "+IN_11") (pintype "input"))
      (node (ref "R24") (pin "2") (pinfunction "S_2") (pintype "passive"))
    )
    (net (code "54") (name "Net-(IC2D--IN)") (class "Default")
      (node (ref "IC2") (pin "10") (pinfunction "-IN_10") (pintype "input"))
      (node (ref "J1") (pin "2") (pinfunction "5_2") (pintype "passive"))
    )
    (net (code "55") (name "Net-(IC3A-+IN)") (class "Default")
      (node (ref "IC3") (pin "5") (pinfunction "+IN_5") (pintype "input"))
      (node (ref "R3") (pin "2") (pinfunction "S_2") (pintype "passive"))
    )
    (net (code "56") (name "Net-(IC3A--IN)") (class "Default")
      (node (ref "IC3") (pin "4") (pinfunction "-IN_4") (pintype "input"))
      (node (ref "J1") (pin "5") (pinfunction "2_5") (pintype "passive"))
    )
    (net (code "57") (name "Net-(IC3A-OUT)") (class "Default")
      (node (ref "ARDUINO_DUE1") (pin "CANTX") (pinfunction "CANTX_CANTX") (pintype "bidirectional"))
      (node (ref "IC3") (pin "2") (pinfunction "OUT_2") (pintype "output"))
      (node (ref "R12") (pin "1") (pinfunction "1_1") (pintype "passive"))
    )
    (net (code "58") (name "Net-(IC3B-+IN)") (class "Default")
      (node (ref "IC3") (pin "7") (pinfunction "+IN_7") (pintype "input"))
      (node (ref "R4") (pin "2") (pinfunction "S_2") (pintype "passive"))
    )
    (net (code "59") (name "Net-(IC3B--IN)") (class "Default")
      (node (ref "IC3") (pin "6") (pinfunction "-IN_6") (pintype "input"))
      (node (ref "J1") (pin "6") (pinfunction "1_6") (pintype "passive"))
    )
    (net (code "60") (name "Net-(IC3B-OUT)") (class "Default")
      (node (ref "ARDUINO_DUE1") (pin "CANRX") (pinfunction "CANRX_CANRX") (pintype "bidirectional"))
      (node (ref "IC3") (pin "1") (pinfunction "OUT_1") (pintype "output"))
      (node (ref "R11") (pin "1") (pinfunction "1_1") (pintype "passive"))
    )
    (net (code "61") (name "Net-(IC4-GND)") (class "Default")
      (node (ref "C1") (pin "-") (pinfunction "-_-") (pintype "passive"))
      (node (ref "C2") (pin "-") (pinfunction "-_-") (pintype "passive"))
      (node (ref "IC4") (pin "2") (pinfunction "GND_2") (pintype "passive"))
      (node (ref "S2") (pin "3") (pinfunction "S_3") (pintype "passive"))
    )
    (net (code "62") (name "Net-(IC4-VI)") (class "Default")
      (node (ref "C1") (pin "+") (pinfunction "+_+") (pintype "passive"))
      (node (ref "IC4") (pin "1") (pinfunction "VI_1") (pintype "input"))
      (node (ref "J6") (pin "5") (pinfunction "5_5") (pintype "passive"))
      (node (ref "J7") (pin "5") (pinfunction "5_5") (pintype "passive"))
      (node (ref "X1") (pin "1") (pinfunction "KL_1") (pintype "passive"))
    )
    (net (code "63") (name "Net-(IC4-VO)") (class "Default")
      (node (ref "C2") (pin "+") (pinfunction "+_+") (pintype "passive"))
      (node (ref "IC4") (pin "3") (pinfunction "VO_3") (pintype "passive"))
      (node (ref "J3") (pin "1") (pinfunction "6_1") (pintype "passive"))
      (node (ref "R6") (pin "1") (pinfunction "1_1") (pintype "passive"))
    )
    (net (code "64") (name "Net-(IC5A-+IN)") (class "Default")
      (node (ref "IC5") (pin "5") (pinfunction "+IN_5") (pintype "input"))
      (node (ref "R26") (pin "2") (pinfunction "S_2") (pintype "passive"))
    )
    (net (code "65") (name "Net-(IC5A--IN)") (class "Default")
      (node (ref "IC5") (pin "4") (pinfunction "-IN_4") (pintype "input"))
      (node (ref "J9") (pin "5") (pinfunction "2_5") (pintype "passive"))
    )
    (net (code "66") (name "Net-(IC5B-+IN)") (class "Default")
      (node (ref "IC5") (pin "7") (pinfunction "+IN_7") (pintype "input"))
      (node (ref "R27") (pin "2") (pinfunction "S_2") (pintype "passive"))
    )
    (net (code "67") (name "Net-(IC5B--IN)") (class "Default")
      (node (ref "IC5") (pin "6") (pinfunction "-IN_6") (pintype "input"))
      (node (ref "J9") (pin "6") (pinfunction "1_6") (pintype "passive"))
    )
    (net (code "68") (name "Net-(IC5C-+IN)") (class "Default")
      (node (ref "IC5") (pin "9") (pinfunction "+IN_9") (pintype "input"))
      (node (ref "R7") (pin "2") (pinfunction "S_2") (pintype "passive"))
    )
    (net (code "69") (name "Net-(IC5C--IN)") (class "Default")
      (node (ref "IC5") (pin "8") (pinfunction "-IN_8") (pintype "input"))
      (node (ref "J9") (pin "3") (pinfunction "4_3") (pintype "passive"))
    )
    (net (code "70") (name "Net-(IC5D-+IN)") (class "Default")
      (node (ref "IC5") (pin "11") (pinfunction "+IN_11") (pintype "input"))
      (node (ref "R15") (pin "2") (pinfunction "S_2") (pintype "passive"))
    )
    (net (code "71") (name "Net-(IC5D--IN)") (class "Default")
      (node (ref "IC5") (pin "10") (pinfunction "-IN_10") (pintype "input"))
      (node (ref "J9") (pin "4") (pinfunction "3_4") (pintype "passive"))
    )
    (net (code "72") (name "Net-(IC6-GND)") (class "Default")
      (node (ref "C3") (pin "-") (pinfunction "-_-") (pintype "passive"))
      (node (ref "C4") (pin "-") (pinfunction "-_-") (pintype "passive"))
      (node (ref "IC6") (pin "2") (pinfunction "GND_2") (pintype "passive"))
      (node (ref "S1") (pin "3") (pinfunction "S_3") (pintype "passive"))
    )
    (net (code "73") (name "Net-(IC6-VI)") (class "Default")
      (node (ref "C3") (pin "+") (pinfunction "+_+") (pintype "passive"))
      (node (ref "IC6") (pin "1") (pinfunction "VI_1") (pintype "input"))
      (node (ref "J10") (pin "5") (pinfunction "5_5") (pintype "passive"))
      (node (ref "J11") (pin "5") (pinfunction "5_5") (pintype "passive"))
      (node (ref "X2") (pin "1") (pinfunction "KL_1") (pintype "passive"))
    )
    (net (code "74") (name "Net-(IC6-VO)") (class "Default")
      (node (ref "C4") (pin "+") (pinfunction "+_+") (pintype "passive"))
      (node (ref "IC6") (pin "3") (pinfunction "VO_3") (pintype "passive"))
      (node (ref "J9") (pin "1") (pinfunction "6_1") (pintype "passive"))
      (node (ref "R32") (pin "1") (pinfunction "1_1") (pintype "passive"))
    )
    (net (code "75") (name "Net-(IC7A-+IN)") (class "Default")
      (node (ref "IC7") (pin "5") (pinfunction "+IN_5") (pintype "input"))
      (node (ref "R16") (pin "2") (pinfunction "S_2") (pintype "passive"))
    )
    (net (code "76") (name "Net-(IC7A--IN)") (class "Default")
      (node (ref "IC7") (pin "4") (pinfunction "-IN_4") (pintype "input"))
      (node (ref "J2") (pin "3") (pinfunction "4_3") (pintype "passive"))
    )
    (net (code "77") (name "Net-(IC7A-OUT)") (class "Default")
      (node (ref "ARDUINO_DUE2") (pin "DAC1") (pinfunction "DAC1_DAC1") (pintype "bidirectional"))
      (node (ref "IC7") (pin "2") (pinfunction "OUT_2") (pintype "output"))
      (node (ref "R35") (pin "1") (pinfunction "1_1") (pintype "passive"))
    )
    (net (code "78") (name "Net-(IC7B-+IN)") (class "Default")
      (node (ref "IC7") (pin "7") (pinfunction "+IN_7") (pintype "input"))
      (node (ref "R25") (pin "2") (pinfunction "S_2") (pintype "passive"))
    )
    (net (code "79") (name "Net-(IC7B--IN)") (class "Default")
      (node (ref "IC7") (pin "6") (pinfunction "-IN_6") (pintype "input"))
      (node (ref "J2") (pin "4") (pinfunction "3_4") (pintype "passive"))
    )
    (net (code "80") (name "Net-(IC7B-OUT)") (class "Default")
      (node (ref "ARDUINO_DUE2") (pin "DAC0") (pinfunction "DAC0_DAC0") (pintype "bidirectional"))
      (node (ref "IC7") (pin "1") (pinfunction "OUT_1") (pintype "output"))
      (node (ref "R34") (pin "1") (pinfunction "1_1") (pintype "passive"))
    )
    (net (code "81") (name "Net-(IC7C-+IN)") (class "Default")
      (node (ref "IC7") (pin "9") (pinfunction "+IN_9") (pintype "input"))
      (node (ref "R28") (pin "2") (pinfunction "S_2") (pintype "passive"))
    )
    (net (code "82") (name "Net-(IC7C--IN)") (class "Default")
      (node (ref "IC7") (pin "8") (pinfunction "-IN_8") (pintype "input"))
      (node (ref "J2") (pin "1") (pinfunction "6_1") (pintype "passive"))
    )
    (net (code "83") (name "Net-(IC7D-+IN)") (class "Default")
      (node (ref "IC7") (pin "11") (pinfunction "+IN_11") (pintype "input"))
      (node (ref "R29") (pin "2") (pinfunction "S_2") (pintype "passive"))
    )
    (net (code "84") (name "Net-(IC7D--IN)") (class "Default")
      (node (ref "IC7") (pin "10") (pinfunction "-IN_10") (pintype "input"))
      (node (ref "J2") (pin "2") (pinfunction "5_2") (pintype "passive"))
    )
    (net (code "85") (name "Net-(IC8A-+IN)") (class "Default")
      (node (ref "IC8") (pin "5") (pinfunction "+IN_5") (pintype "input"))
      (node (ref "R30") (pin "2") (pinfunction "S_2") (pintype "passive"))
    )
    (net (code "86") (name "Net-(IC8A--IN)") (class "Default")
      (node (ref "IC8") (pin "4") (pinfunction "-IN_4") (pintype "input"))
      (node (ref "J2") (pin "5") (pinfunction "2_5") (pintype "passive"))
    )
    (net (code "87") (name "Net-(IC8A-OUT)") (class "Default")
      (node (ref "ARDUINO_DUE2") (pin "CANTX") (pinfunction "CANTX_CANTX") (pintype "bidirectional"))
      (node (ref "IC8") (pin "2") (pinfunction "OUT_2") (pintype "output"))
      (node (ref "R40") (pin "1") (pinfunction "1_1") (pintype "passive"))
    )
    (net (code "88") (name "Net-(IC8B-+IN)") (class "Default")
      (node (ref "IC8") (pin "7") (pinfunction "+IN_7") (pintype "input"))
      (node (ref "R31") (pin "2") (pinfunction "S_2") (pintype "passive"))
    )
    (net (code "89") (name "Net-(IC8B--IN)") (class "Default")
      (node (ref "IC8") (pin "6") (pinfunction "-IN_6") (pintype "input"))
      (node (ref "J2") (pin "6") (pinfunction "1_6") (pintype "passive"))
    )
    (net (code "90") (name "Net-(IC8B-OUT)") (class "Default")
      (node (ref "ARDUINO_DUE2") (pin "CANRX") (pinfunction "CANRX_CANRX") (pintype "bidirectional"))
      (node (ref "IC8") (pin "1") (pinfunction "OUT_1") (pintype "output"))
      (node (ref "R39") (pin "1") (pinfunction "1_1") (pintype "passive"))
    )
    (net (code "91") (name "Net-(J3-5)") (class "Default")
      (node (ref "ARDUINO_DUE1") (pin "GND_1") (pinfunction "GND_GND_1") (pintype "bidirectional"))
      (node (ref "J3") (pin "2") (pinfunction "5_2") (pintype "passive"))
      (node (ref "J7") (pin "3") (pinfunction "3_3") (pintype "passive"))
      (node (ref "LED1") (pin "K") (pinfunction "C_K") (pintype "passive"))
      (node (ref "LED10") (pin "K") (pinfunction "C_K") (pintype "passive"))
      (node (ref "LED2") (pin "K") (pinfunction "C_K") (pintype "passive"))
      (node (ref "LED3") (pin "K") (pinfunction "C_K") (pintype "passive"))
      (node (ref "LED4") (pin "K") (pinfunction "C_K") (pintype "passive"))
      (node (ref "LED5") (pin "K") (pinfunction "C_K") (pintype "passive"))
      (node (ref "LED6") (pin "K") (pinfunction "C_K") (pintype "passive"))
      (node (ref "LED7") (pin "K") (pinfunction "C_K") (pintype "passive"))
      (node (ref "LED8") (pin "K") (pinfunction "C_K") (pintype "passive"))
      (node (ref "LED9") (pin "K") (pinfunction "C_K") (pintype "passive"))
      (node (ref "R17") (pin "3") (pinfunction "E_3") (pintype "passive"))
      (node (ref "R18") (pin "3") (pinfunction "E_3") (pintype "passive"))
      (node (ref "R19") (pin "3") (pinfunction "E_3") (pintype "passive"))
      (node (ref "R20") (pin "3") (pinfunction "E_3") (pintype "passive"))
      (node (ref "R21") (pin "3") (pinfunction "E_3") (pintype "passive"))
      (node (ref "R22") (pin "3") (pinfunction "E_3") (pintype "passive"))
      (node (ref "R23") (pin "3") (pinfunction "E_3") (pintype "passive"))
      (node (ref "R24") (pin "3") (pinfunction "E_3") (pintype "passive"))
      (node (ref "R3") (pin "3") (pinfunction "E_3") (pintype "passive"))
      (node (ref "R4") (pin "3") (pinfunction "E_3") (pintype "passive"))
      (node (ref "S2") (pin "2") (pinfunction "P_2") (pintype "passive"))
      (node (ref "S3") (pin "3") (pinfunction "P_3") (pintype "passive"))
      (node (ref "X1") (pin "2") (pinfunction "KL_2") (pintype "passive"))
    )
    (net (code "92") (name "Net-(J9-5)") (class "Default")
      (node (ref "ARDUINO_DUE2") (pin "GND_1") (pinfunction "GND_GND_1") (pintype "bidirectional"))
      (node (ref "J11") (pin "3") (pinfunction "3_3") (pintype "passive"))
      (node (ref "J9") (pin "2") (pinfunction "5_2") (pintype "passive"))
      (node (ref "LED11") (pin "K") (pinfunction "C_K") (pintype "passive"))
      (node (ref "LED12") (pin "K") (pinfunction "C_K") (pintype "passive"))
      (node (ref "LED13") (pin "K") (pinfunction "C_K") (pintype "passive"))
      (node (ref "LED14") (pin "K") (pinfunction "C_K") (pintype "passive"))
      (node (ref "LED15") (pin "K") (pinfunction "C_K") (pintype "passive"))
      (node (ref "LED16") (pin "K") (pinfunction "C_K") (pintype "passive"))
      (node (ref "LED17") (pin "K") (pinfunction "C_K") (pintype "passive"))
      (node (ref "LED18") (pin "K") (pinfunction "C_K") (pintype "passive"))
      (node (ref "LED19") (pin "K") (pinfunction "C_K") (pintype "passive"))
      (node (ref "LED20") (pin "K") (pinfunction "C_K") (pintype "passive"))
      (node (ref "R15") (pin "3") (pinfunction "E_3") (pintype "passive"))
      (node (ref "R16") (pin "3") (pinfunction "E_3") (pintype "passive"))
      (node (ref "R25") (pin "3") (pinfunction "E_3") (pintype "passive"))
      (node (ref "R26") (pin "3") (pinfunction "E_3") (pintype "passive"))
      (node (ref "R27") (pin "3") (pinfunction "E_3") (pintype "passive"))
      (node (ref "R28") (pin "3") (pinfunction "E_3") (pintype "passive"))
      (node (ref "R29") (pin "3") (pinfunction "E_3") (pintype "passive"))
      (node (ref "R30") (pin "3") (pinfunction "E_3") (pintype "passive"))
      (node (ref "R31") (pin "3") (pinfunction "E_3") (pintype "passive"))
      (node (ref "R7") (pin "3") (pinfunction "E_3") (pintype "passive"))
      (node (ref "S1") (pin "2") (pinfunction "P_2") (pintype "passive"))
      (node (ref "S4") (pin "3") (pinfunction "P_3") (pintype "passive"))
      (node (ref "X2") (pin "2") (pinfunction "KL_2") (pintype "passive"))
    )
    (net (code "93") (name "Net-(LED1-PadA)") (class "Default")
      (node (ref "LED1") (pin "A") (pinfunction "A_A") (pintype "passive"))
      (node (ref "R13") (pin "2") (pinfunction "2_2") (pintype "passive"))
    )
    (net (code "94") (name "Net-(LED2-PadA)") (class "Default")
      (node (ref "LED2") (pin "A") (pinfunction "A_A") (pintype "passive"))
      (node (ref "R9") (pin "2") (pinfunction "2_2") (pintype "passive"))
    )
    (net (code "95") (name "Net-(LED3-PadA)") (class "Default")
      (node (ref "LED3") (pin "A") (pinfunction "A_A") (pintype "passive"))
      (node (ref "R14") (pin "2") (pinfunction "2_2") (pintype "passive"))
    )
    (net (code "96") (name "Net-(LED4-PadA)") (class "Default")
      (node (ref "LED4") (pin "A") (pinfunction "A_A") (pintype "passive"))
      (node (ref "R8") (pin "2") (pinfunction "2_2") (pintype "passive"))
    )
    (net (code "97") (name "Net-(LED5-PadA)") (class "Default")
      (node (ref "LED5") (pin "A") (pinfunction "A_A") (pintype "passive"))
      (node (ref "R2") (pin "2") (pinfunction "2_2") (pintype "passive"))
    )
    (net (code "98") (name "Net-(LED6-PadA)") (class "Default")
      (node (ref "LED6") (pin "A") (pinfunction "A_A") (pintype "passive"))
      (node (ref "R1") (pin "2") (pinfunction "2_2") (pintype "passive"))
    )
    (net (code "99") (name "Net-(LED7-PadA)") (class "Default")
      (node (ref "LED7") (pin "A") (pinfunction "A_A") (pintype "passive"))
      (node (ref "R5") (pin "2") (pinfunction "2_2") (pintype "passive"))
    )
    (net (code "100") (name "Net-(LED8-PadA)") (class "Default")
      (node (ref "LED8") (pin "A") (pinfunction "A_A") (pintype "passive"))
      (node (ref "R10") (pin "2") (pinfunction "2_2") (pintype "passive"))
    )
    (net (code "101") (name "Net-(LED9-PadA)") (class "Default")
      (node (ref "LED9") (pin "A") (pinfunction "A_A") (pintype "passive"))
      (node (ref "R12") (pin "2") (pinfunction "2_2") (pintype "passive"))
    )
    (net (code "102") (name "Net-(LED10-PadA)") (class "Default")
      (node (ref "LED10") (pin "A") (pinfunction "A_A") (pintype "passive"))
      (node (ref "R11") (pin "2") (pinfunction "2_2") (pintype "passive"))
    )
    (net (code "103") (name "Net-(LED11-PadA)") (class "Default")
      (node (ref "LED11") (pin "A") (pinfunction "A_A") (pintype "passive"))
      (node (ref "R41") (pin "2") (pinfunction "2_2") (pintype "passive"))
    )
    (net (code "104") (name "Net-(LED12-PadA)") (class "Default")
      (node (ref "LED12") (pin "A") (pinfunction "A_A") (pintype "passive"))
      (node (ref "R42") (pin "2") (pinfunction "2_2") (pintype "passive"))
    )
    (net (code "105") (name "Net-(LED13-PadA)") (class "Default")
      (node (ref "LED13") (pin "A") (pinfunction "A_A") (pintype "passive"))
      (node (ref "R36") (pin "2") (pinfunction "2_2") (pintype "passive"))
    )
    (net (code "106") (name "Net-(LED14-PadA)") (class "Default")
      (node (ref "LED14") (pin "A") (pinfunction "A_A") (pintype "passive"))
      (node (ref "R35") (pin "2") (pinfunction "2_2") (pintype "passive"))
    )
    (net (code "107") (name "Net-(LED15-PadA)") (class "Default")
      (node (ref "LED15") (pin "A") (pinfunction "A_A") (pintype "passive"))
      (node (ref "R34") (pin "2") (pinfunction "2_2") (pintype "passive"))
    )
    (net (code "108") (name "Net-(LED16-PadA)") (class "Default")
      (node (ref "LED16") (pin "A") (pinfunction "A_A") (pintype "passive"))
      (node (ref "R33") (pin "2") (pinfunction "2_2") (pintype "passive"))
    )
    (net (code "109") (name "Net-(LED17-PadA)") (class "Default")
      (node (ref "LED17") (pin "A") (pinfunction "A_A") (pintype "passive"))
      (node (ref "R38") (pin "2") (pinfunction "2_2") (pintype "passive"))
    )
    (net (code "110") (name "Net-(LED18-PadA)") (class "Default")
      (node (ref "LED18") (pin "A") (pinfunction "A_A") (pintype "passive"))
      (node (ref "R37") (pin "2") (pinfunction "2_2") (pintype "passive"))
    )
    (net (code "111") (name "Net-(LED19-PadA)") (class "Default")
      (node (ref "LED19") (pin "A") (pinfunction "A_A") (pintype "passive"))
      (node (ref "R40") (pin "2") (pinfunction "2_2") (pintype "passive"))
    )
    (net (code "112") (name "Net-(LED20-PadA)") (class "Default")
      (node (ref "LED20") (pin "A") (pinfunction "A_A") (pintype "passive"))
      (node (ref "R39") (pin "2") (pinfunction "2_2") (pintype "passive"))
    )
    (net (code "113") (name "Net-(R15-A)") (class "Default")
      (node (ref "ARDUINO_DUE2") (pin "5V0") (pinfunction "5V_5V0") (pintype "bidirectional"))
      (node (ref "R15") (pin "1") (pinfunction "A_1") (pintype "passive"))
      (node (ref "R16") (pin "1") (pinfunction "A_1") (pintype "passive"))
      (node (ref "R25") (pin "1") (pinfunction "A_1") (pintype "passive"))
      (node (ref "R26") (pin "1") (pinfunction "A_1") (pintype "passive"))
      (node (ref "R27") (pin "1") (pinfunction "A_1") (pintype "passive"))
      (node (ref "R28") (pin "1") (pinfunction "A_1") (pintype "passive"))
      (node (ref "R29") (pin "1") (pinfunction "A_1") (pintype "passive"))
      (node (ref "R30") (pin "1") (pinfunction "A_1") (pintype "passive"))
      (node (ref "R31") (pin "1") (pinfunction "A_1") (pintype "passive"))
      (node (ref "R7") (pin "1") (pinfunction "A_1") (pintype "passive"))
    )
    (net (code "114") (name "Net-(R17-A)") (class "Default")
      (node (ref "ARDUINO_DUE1") (pin "5V0") (pinfunction "5V_5V0") (pintype "bidirectional"))
      (node (ref "R17") (pin "1") (pinfunction "A_1") (pintype "passive"))
      (node (ref "R18") (pin "1") (pinfunction "A_1") (pintype "passive"))
      (node (ref "R19") (pin "1") (pinfunction "A_1") (pintype "passive"))
      (node (ref "R20") (pin "1") (pinfunction "A_1") (pintype "passive"))
      (node (ref "R21") (pin "1") (pinfunction "A_1") (pintype "passive"))
      (node (ref "R22") (pin "1") (pinfunction "A_1") (pintype "passive"))
      (node (ref "R23") (pin "1") (pinfunction "A_1") (pintype "passive"))
      (node (ref "R24") (pin "1") (pinfunction "A_1") (pintype "passive"))
      (node (ref "R3") (pin "1") (pinfunction "A_1") (pintype "passive"))
      (node (ref "R4") (pin "1") (pinfunction "A_1") (pintype "passive"))
    )
    (net (code "115") (name "Net-(S3-S1)") (class "Default")
      (node (ref "ARDUINO_DUE1") (pin "RESET") (pinfunction "RESET_RESET") (pintype "bidirectional"))
      (node (ref "R6") (pin "2") (pinfunction "2_2") (pintype "passive"))
      (node (ref "S3") (pin "2") (pinfunction "S1_2") (pintype "passive"))
    )
    (net (code "116") (name "Net-(S4-S1)") (class "Default")
      (node (ref "ARDUINO_DUE2") (pin "RESET") (pinfunction "RESET_RESET") (pintype "bidirectional"))
      (node (ref "R32") (pin "2") (pinfunction "2_2") (pintype "passive"))
      (node (ref "S4") (pin "2") (pinfunction "S1_2") (pintype "passive"))
    )
    (net (code "117") (name "unconnected-(ARDUINO_DUE1-5V-Pad5V0_2)") (class "Default")
      (node (ref "ARDUINO_DUE1") (pin "5V0_2") (pinfunction "5V_5V0_2") (pintype "bidirectional"))
    )
    (net (code "118") (name "unconnected-(ARDUINO_DUE1-AN2-PadA2)") (class "Default")
      (node (ref "ARDUINO_DUE1") (pin "A2") (pinfunction "AN2_A2") (pintype "bidirectional"))
    )
    (net (code "119") (name "unconnected-(ARDUINO_DUE1-AN3-PadA3)") (class "Default")
      (node (ref "ARDUINO_DUE1") (pin "A3") (pinfunction "AN3_A3") (pintype "bidirectional"))
    )
    (net (code "120") (name "unconnected-(ARDUINO_DUE1-AN6-PadA6)") (class "Default")
      (node (ref "ARDUINO_DUE1") (pin "A6") (pinfunction "AN6_A6") (pintype "bidirectional"))
    )
    (net (code "121") (name "unconnected-(ARDUINO_DUE1-AN7-PadA7)") (class "Default")
      (node (ref "ARDUINO_DUE1") (pin "A7") (pinfunction "AN7_A7") (pintype "bidirectional"))
    )
    (net (code "122") (name "unconnected-(ARDUINO_DUE1-AN10-PadA10)") (class "Default")
      (node (ref "ARDUINO_DUE1") (pin "A10") (pinfunction "AN10_A10") (pintype "bidirectional"))
    )
    (net (code "123") (name "unconnected-(ARDUINO_DUE1-AN11-PadA11)") (class "Default")
      (node (ref "ARDUINO_DUE1") (pin "A11") (pinfunction "AN11_A11") (pintype "bidirectional"))
    )
    (net (code "124") (name "unconnected-(ARDUINO_DUE1-GND-PadGND_2)") (class "Default")
      (node (ref "ARDUINO_DUE1") (pin "GND_2") (pinfunction "GND_GND_2") (pintype "bidirectional"))
    )
    (net (code "125") (name "unconnected-(ARDUINO_DUE1-GND-PadGND_4)") (class "Default")
      (node (ref "ARDUINO_DUE1") (pin "GND_4") (pinfunction "GND_GND_4") (pintype "bidirectional"))
    )
    (net (code "126") (name "unconnected-(ARDUINO_DUE1-NC-PadNC_2)") (class "Default")
      (node (ref "ARDUINO_DUE1") (pin "NC_2") (pinfunction "NC_NC_2") (pintype "no_connect"))
    )
    (net (code "127") (name "unconnected-(ARDUINO_DUE1-Pad3V3)") (class "Default")
      (node (ref "ARDUINO_DUE1") (pin "3V3") (pinfunction "3V3_3V3") (pintype "bidirectional"))
    )
    (net (code "128") (name "unconnected-(ARDUINO_DUE1-Pad8)") (class "Default")
      (node (ref "ARDUINO_DUE1") (pin "8") (pinfunction "8_8") (pintype "bidirectional"))
    )
    (net (code "129") (name "unconnected-(ARDUINO_DUE1-Pad9)") (class "Default")
      (node (ref "ARDUINO_DUE1") (pin "9") (pinfunction "9_9") (pintype "bidirectional"))
    )
    (net (code "130") (name "unconnected-(ARDUINO_DUE1-Pad10)") (class "Default")
      (node (ref "ARDUINO_DUE1") (pin "10") (pinfunction "10_10") (pintype "bidirectional"))
    )
    (net (code "131") (name "unconnected-(ARDUINO_DUE1-Pad11)") (class "Default")
      (node (ref "ARDUINO_DUE1") (pin "11") (pinfunction "11_11") (pintype "bidirectional"))
    )
    (net (code "132") (name "unconnected-(ARDUINO_DUE1-Pad22)") (class "Default")
      (node (ref "ARDUINO_DUE1") (pin "22") (pinfunction "22_22") (pintype "bidirectional"))
    )
    (net (code "133") (name "unconnected-(ARDUINO_DUE1-Pad23)") (class "Default")
      (node (ref "ARDUINO_DUE1") (pin "23") (pinfunction "23_23") (pintype "bidirectional"))
    )
    (net (code "134") (name "unconnected-(ARDUINO_DUE1-Pad24)") (class "Default")
      (node (ref "ARDUINO_DUE1") (pin "24") (pinfunction "24_24") (pintype "bidirectional"))
    )
    (net (code "135") (name "unconnected-(ARDUINO_DUE1-Pad25)") (class "Default")
      (node (ref "ARDUINO_DUE1") (pin "25") (pinfunction "25_25") (pintype "bidirectional"))
    )
    (net (code "136") (name "unconnected-(ARDUINO_DUE1-Pad26)") (class "Default")
      (node (ref "ARDUINO_DUE1") (pin "26") (pinfunction "26_26") (pintype "bidirectional"))
    )
    (net (code "137") (name "unconnected-(ARDUINO_DUE1-Pad27)") (class "Default")
      (node (ref "ARDUINO_DUE1") (pin "27") (pinfunction "27_27") (pintype "bidirectional"))
    )
    (net (code "138") (name "unconnected-(ARDUINO_DUE1-Pad28)") (class "Default")
      (node (ref "ARDUINO_DUE1") (pin "28") (pinfunction "28_28") (pintype "bidirectional"))
    )
    (net (code "139") (name "unconnected-(ARDUINO_DUE1-Pad29)") (class "Default")
      (node (ref "ARDUINO_DUE1") (pin "29") (pinfunction "29_29") (pintype "bidirectional"))
    )
    (net (code "140") (name "unconnected-(ARDUINO_DUE1-Pad30)") (class "Default")
      (node (ref "ARDUINO_DUE1") (pin "30") (pinfunction "30_30") (pintype "bidirectional"))
    )
    (net (code "141") (name "unconnected-(ARDUINO_DUE1-Pad31)") (class "Default")
      (node (ref "ARDUINO_DUE1") (pin "31") (pinfunction "31_31") (pintype "bidirectional"))
    )
    (net (code "142") (name "unconnected-(ARDUINO_DUE1-Pad32)") (class "Default")
      (node (ref "ARDUINO_DUE1") (pin "32") (pinfunction "32_32") (pintype "bidirectional"))
    )
    (net (code "143") (name "unconnected-(ARDUINO_DUE1-Pad33)") (class "Default")
      (node (ref "ARDUINO_DUE1") (pin "33") (pinfunction "33_33") (pintype "bidirectional"))
    )
    (net (code "144") (name "unconnected-(ARDUINO_DUE1-Pad34)") (class "Default")
      (node (ref "ARDUINO_DUE1") (pin "34") (pinfunction "34_34") (pintype "bidirectional"))
    )
    (net (code "145") (name "unconnected-(ARDUINO_DUE1-Pad35)") (class "Default")
      (node (ref "ARDUINO_DUE1") (pin "35") (pinfunction "35_35") (pintype "bidirectional"))
    )
    (net (code "146") (name "unconnected-(ARDUINO_DUE1-Pad36)") (class "Default")
      (node (ref "ARDUINO_DUE1") (pin "36") (pinfunction "36_36") (pintype "bidirectional"))
    )
    (net (code "147") (name "unconnected-(ARDUINO_DUE1-Pad37)") (class "Default")
      (node (ref "ARDUINO_DUE1") (pin "37") (pinfunction "37_37") (pintype "bidirectional"))
    )
    (net (code "148") (name "unconnected-(ARDUINO_DUE1-Pad38)") (class "Default")
      (node (ref "ARDUINO_DUE1") (pin "38") (pinfunction "38_38") (pintype "bidirectional"))
    )
    (net (code "149") (name "unconnected-(ARDUINO_DUE1-Pad39)") (class "Default")
      (node (ref "ARDUINO_DUE1") (pin "39") (pinfunction "39_39") (pintype "bidirectional"))
    )
    (net (code "150") (name "unconnected-(ARDUINO_DUE1-Pad40)") (class "Default")
      (node (ref "ARDUINO_DUE1") (pin "40") (pinfunction "40_40") (pintype "bidirectional"))
    )
    (net (code "151") (name "unconnected-(ARDUINO_DUE1-Pad41)") (class "Default")
      (node (ref "ARDUINO_DUE1") (pin "41") (pinfunction "41_41") (pintype "bidirectional"))
    )
    (net (code "152") (name "unconnected-(ARDUINO_DUE1-Pad42)") (class "Default")
      (node (ref "ARDUINO_DUE1") (pin "42") (pinfunction "42_42") (pintype "bidirectional"))
    )
    (net (code "153") (name "unconnected-(ARDUINO_DUE1-Pad43)") (class "Default")
      (node (ref "ARDUINO_DUE1") (pin "43") (pinfunction "43_43") (pintype "bidirectional"))
    )
    (net (code "154") (name "unconnected-(ARDUINO_DUE1-Pad44)") (class "Default")
      (node (ref "ARDUINO_DUE1") (pin "44") (pinfunction "44_44") (pintype "bidirectional"))
    )
    (net (code "155") (name "unconnected-(ARDUINO_DUE1-Pad45)") (class "Default")
      (node (ref "ARDUINO_DUE1") (pin "45") (pinfunction "45_45") (pintype "bidirectional"))
    )
    (net (code "156") (name "unconnected-(ARDUINO_DUE1-Pad46)") (class "Default")
      (node (ref "ARDUINO_DUE1") (pin "46") (pinfunction "46_46") (pintype "bidirectional"))
    )
    (net (code "157") (name "unconnected-(ARDUINO_DUE1-Pad47)") (class "Default")
      (node (ref "ARDUINO_DUE1") (pin "47") (pinfunction "47_47") (pintype "bidirectional"))
    )
    (net (code "158") (name "unconnected-(ARDUINO_DUE1-Pad48)") (class "Default")
      (node (ref "ARDUINO_DUE1") (pin "48") (pinfunction "48_48") (pintype "bidirectional"))
    )
    (net (code "159") (name "unconnected-(ARDUINO_DUE1-Pad49)") (class "Default")
      (node (ref "ARDUINO_DUE1") (pin "49") (pinfunction "49_49") (pintype "bidirectional"))
    )
    (net (code "160") (name "unconnected-(ARDUINO_DUE1-Pad50)") (class "Default")
      (node (ref "ARDUINO_DUE1") (pin "50") (pinfunction "50_50") (pintype "bidirectional"))
    )
    (net (code "161") (name "unconnected-(ARDUINO_DUE1-Pad51)") (class "Default")
      (node (ref "ARDUINO_DUE1") (pin "51") (pinfunction "51_51") (pintype "bidirectional"))
    )
    (net (code "162") (name "unconnected-(ARDUINO_DUE1-Pad52)") (class "Default")
      (node (ref "ARDUINO_DUE1") (pin "52") (pinfunction "52_52") (pintype "bidirectional"))
    )
    (net (code "163") (name "unconnected-(ARDUINO_DUE1-Pad53)") (class "Default")
      (node (ref "ARDUINO_DUE1") (pin "53") (pinfunction "53_53") (pintype "bidirectional"))
    )
    (net (code "164") (name "unconnected-(ARDUINO_DUE1-PadAREF)") (class "Default")
      (node (ref "ARDUINO_DUE1") (pin "AREF") (pinfunction "AREF_AREF") (pintype "bidirectional"))
    )
    (net (code "165") (name "unconnected-(ARDUINO_DUE1-PadGND)") (class "Default")
      (node (ref "ARDUINO_DUE1") (pin "GND") (pinfunction "GND_GND") (pintype "bidirectional"))
    )
    (net (code "166") (name "unconnected-(ARDUINO_DUE1-PadIOREF)") (class "Default")
      (node (ref "ARDUINO_DUE1") (pin "IOREF") (pinfunction "IOREF_IOREF") (pintype "bidirectional"))
    )
    (net (code "167") (name "unconnected-(ARDUINO_DUE1-PadSCL1)") (class "Default")
      (node (ref "ARDUINO_DUE1") (pin "SCL1") (pinfunction "SCL1_SCL1") (pintype "bidirectional"))
    )
    (net (code "168") (name "unconnected-(ARDUINO_DUE1-PadSDA1)") (class "Default")
      (node (ref "ARDUINO_DUE1") (pin "SDA1") (pinfunction "SDA1_SDA1") (pintype "bidirectional"))
    )
    (net (code "169") (name "unconnected-(ARDUINO_DUE1-PadVIN)") (class "Default")
      (node (ref "ARDUINO_DUE1") (pin "VIN") (pinfunction "VIN_VIN") (pintype "bidirectional"))
    )
    (net (code "170") (name "unconnected-(ARDUINO_DUE1-RX0<0-Pad0)") (class "Default")
      (node (ref "ARDUINO_DUE1") (pin "0") (pinfunction "RX0<0_0") (pintype "bidirectional"))
    )
    (net (code "171") (name "unconnected-(ARDUINO_DUE1-RX2_17-Pad17)") (class "Default")
      (node (ref "ARDUINO_DUE1") (pin "17") (pinfunction "RX2_17_17") (pintype "bidirectional"))
    )
    (net (code "172") (name "unconnected-(ARDUINO_DUE1-RX3_15-Pad15)") (class "Default")
      (node (ref "ARDUINO_DUE1") (pin "15") (pinfunction "RX3_15_15") (pintype "bidirectional"))
    )
    (net (code "173") (name "unconnected-(ARDUINO_DUE1-SCL_21-Pad21)") (class "Default")
      (node (ref "ARDUINO_DUE1") (pin "21") (pinfunction "SCL_21_21") (pintype "bidirectional"))
    )
    (net (code "174") (name "unconnected-(ARDUINO_DUE1-SDA_20-Pad20)") (class "Default")
      (node (ref "ARDUINO_DUE1") (pin "20") (pinfunction "SDA_20_20") (pintype "bidirectional"))
    )
    (net (code "175") (name "unconnected-(ARDUINO_DUE1-TX0>1-Pad1)") (class "Default")
      (node (ref "ARDUINO_DUE1") (pin "1") (pinfunction "TX0>1_1") (pintype "bidirectional"))
    )
    (net (code "176") (name "unconnected-(ARDUINO_DUE1-TX2_16-Pad16)") (class "Default")
      (node (ref "ARDUINO_DUE1") (pin "16") (pinfunction "TX2_16_16") (pintype "bidirectional"))
    )
    (net (code "177") (name "unconnected-(ARDUINO_DUE1-TX3_14-Pad14)") (class "Default")
      (node (ref "ARDUINO_DUE1") (pin "14") (pinfunction "TX3_14_14") (pintype "bidirectional"))
    )
    (net (code "178") (name "unconnected-(ARDUINO_DUE2-5V-Pad5V0_2)") (class "Default")
      (node (ref "ARDUINO_DUE2") (pin "5V0_2") (pinfunction "5V_5V0_2") (pintype "bidirectional"))
    )
    (net (code "179") (name "unconnected-(ARDUINO_DUE2-AN2-PadA2)") (class "Default")
      (node (ref "ARDUINO_DUE2") (pin "A2") (pinfunction "AN2_A2") (pintype "bidirectional"))
    )
    (net (code "180") (name "unconnected-(ARDUINO_DUE2-AN3-PadA3)") (class "Default")
      (node (ref "ARDUINO_DUE2") (pin "A3") (pinfunction "AN3_A3") (pintype "bidirectional"))
    )
    (net (code "181") (name "unconnected-(ARDUINO_DUE2-AN6-PadA6)") (class "Default")
      (node (ref "ARDUINO_DUE2") (pin "A6") (pinfunction "AN6_A6") (pintype "bidirectional"))
    )
    (net (code "182") (name "unconnected-(ARDUINO_DUE2-AN7-PadA7)") (class "Default")
      (node (ref "ARDUINO_DUE2") (pin "A7") (pinfunction "AN7_A7") (pintype "bidirectional"))
    )
    (net (code "183") (name "unconnected-(ARDUINO_DUE2-AN10-PadA10)") (class "Default")
      (node (ref "ARDUINO_DUE2") (pin "A10") (pinfunction "AN10_A10") (pintype "bidirectional"))
    )
    (net (code "184") (name "unconnected-(ARDUINO_DUE2-AN11-PadA11)") (class "Default")
      (node (ref "ARDUINO_DUE2") (pin "A11") (pinfunction "AN11_A11") (pintype "bidirectional"))
    )
    (net (code "185") (name "unconnected-(ARDUINO_DUE2-GND-PadGND_2)") (class "Default")
      (node (ref "ARDUINO_DUE2") (pin "GND_2") (pinfunction "GND_GND_2") (pintype "bidirectional"))
    )
    (net (code "186") (name "unconnected-(ARDUINO_DUE2-GND-PadGND_4)") (class "Default")
      (node (ref "ARDUINO_DUE2") (pin "GND_4") (pinfunction "GND_GND_4") (pintype "bidirectional"))
    )
    (net (code "187") (name "unconnected-(ARDUINO_DUE2-NC-PadNC_2)") (class "Default")
      (node (ref "ARDUINO_DUE2") (pin "NC_2") (pinfunction "NC_NC_2") (pintype "no_connect"))
    )
    (net (code "188") (name "unconnected-(ARDUINO_DUE2-Pad3V3)") (class "Default")
      (node (ref "ARDUINO_DUE2") (pin "3V3") (pinfunction "3V3_3V3") (pintype "bidirectional"))
    )
    (net (code "189") (name "unconnected-(ARDUINO_DUE2-Pad8)") (class "Default")
      (node (ref "ARDUINO_DUE2") (pin "8") (pinfunction "8_8") (pintype "bidirectional"))
    )
    (net (code "190") (name "unconnected-(ARDUINO_DUE2-Pad9)") (class "Default")
      (node (ref "ARDUINO_DUE2") (pin "9") (pinfunction "9_9") (pintype "bidirectional"))
    )
    (net (code "191") (name "unconnected-(ARDUINO_DUE2-Pad10)") (class "Default")
      (node (ref "ARDUINO_DUE2") (pin "10") (pinfunction "10_10") (pintype "bidirectional"))
    )
    (net (code "192") (name "unconnected-(ARDUINO_DUE2-Pad11)") (class "Default")
      (node (ref "ARDUINO_DUE2") (pin "11") (pinfunction "11_11") (pintype "bidirectional"))
    )
    (net (code "193") (name "unconnected-(ARDUINO_DUE2-Pad22)") (class "Default")
      (node (ref "ARDUINO_DUE2") (pin "22") (pinfunction "22_22") (pintype "bidirectional"))
    )
    (net (code "194") (name "unconnected-(ARDUINO_DUE2-Pad23)") (class "Default")
      (node (ref "ARDUINO_DUE2") (pin "23") (pinfunction "23_23") (pintype "bidirectional"))
    )
    (net (code "195") (name "unconnected-(ARDUINO_DUE2-Pad24)") (class "Default")
      (node (ref "ARDUINO_DUE2") (pin "24") (pinfunction "24_24") (pintype "bidirectional"))
    )
    (net (code "196") (name "unconnected-(ARDUINO_DUE2-Pad25)") (class "Default")
      (node (ref "ARDUINO_DUE2") (pin "25") (pinfunction "25_25") (pintype "bidirectional"))
    )
    (net (code "197") (name "unconnected-(ARDUINO_DUE2-Pad26)") (class "Default")
      (node (ref "ARDUINO_DUE2") (pin "26") (pinfunction "26_26") (pintype "bidirectional"))
    )
    (net (code "198") (name "unconnected-(ARDUINO_DUE2-Pad27)") (class "Default")
      (node (ref "ARDUINO_DUE2") (pin "27") (pinfunction "27_27") (pintype "bidirectional"))
    )
    (net (code "199") (name "unconnected-(ARDUINO_DUE2-Pad28)") (class "Default")
      (node (ref "ARDUINO_DUE2") (pin "28") (pinfunction "28_28") (pintype "bidirectional"))
    )
    (net (code "200") (name "unconnected-(ARDUINO_DUE2-Pad29)") (class "Default")
      (node (ref "ARDUINO_DUE2") (pin "29") (pinfunction "29_29") (pintype "bidirectional"))
    )
    (net (code "201") (name "unconnected-(ARDUINO_DUE2-Pad30)") (class "Default")
      (node (ref "ARDUINO_DUE2") (pin "30") (pinfunction "30_30") (pintype "bidirectional"))
    )
    (net (code "202") (name "unconnected-(ARDUINO_DUE2-Pad31)") (class "Default")
      (node (ref "ARDUINO_DUE2") (pin "31") (pinfunction "31_31") (pintype "bidirectional"))
    )
    (net (code "203") (name "unconnected-(ARDUINO_DUE2-Pad32)") (class "Default")
      (node (ref "ARDUINO_DUE2") (pin "32") (pinfunction "32_32") (pintype "bidirectional"))
    )
    (net (code "204") (name "unconnected-(ARDUINO_DUE2-Pad33)") (class "Default")
      (node (ref "ARDUINO_DUE2") (pin "33") (pinfunction "33_33") (pintype "bidirectional"))
    )
    (net (code "205") (name "unconnected-(ARDUINO_DUE2-Pad34)") (class "Default")
      (node (ref "ARDUINO_DUE2") (pin "34") (pinfunction "34_34") (pintype "bidirectional"))
    )
    (net (code "206") (name "unconnected-(ARDUINO_DUE2-Pad35)") (class "Default")
      (node (ref "ARDUINO_DUE2") (pin "35") (pinfunction "35_35") (pintype "bidirectional"))
    )
    (net (code "207") (name "unconnected-(ARDUINO_DUE2-Pad36)") (class "Default")
      (node (ref "ARDUINO_DUE2") (pin "36") (pinfunction "36_36") (pintype "bidirectional"))
    )
    (net (code "208") (name "unconnected-(ARDUINO_DUE2-Pad37)") (class "Default")
      (node (ref "ARDUINO_DUE2") (pin "37") (pinfunction "37_37") (pintype "bidirectional"))
    )
    (net (code "209") (name "unconnected-(ARDUINO_DUE2-Pad38)") (class "Default")
      (node (ref "ARDUINO_DUE2") (pin "38") (pinfunction "38_38") (pintype "bidirectional"))
    )
    (net (code "210") (name "unconnected-(ARDUINO_DUE2-Pad39)") (class "Default")
      (node (ref "ARDUINO_DUE2") (pin "39") (pinfunction "39_39") (pintype "bidirectional"))
    )
    (net (code "211") (name "unconnected-(ARDUINO_DUE2-Pad40)") (class "Default")
      (node (ref "ARDUINO_DUE2") (pin "40") (pinfunction "40_40") (pintype "bidirectional"))
    )
    (net (code "212") (name "unconnected-(ARDUINO_DUE2-Pad41)") (class "Default")
      (node (ref "ARDUINO_DUE2") (pin "41") (pinfunction "41_41") (pintype "bidirectional"))
    )
    (net (code "213") (name "unconnected-(ARDUINO_DUE2-Pad42)") (class "Default")
      (node (ref "ARDUINO_DUE2") (pin "42") (pinfunction "42_42") (pintype "bidirectional"))
    )
    (net (code "214") (name "unconnected-(ARDUINO_DUE2-Pad43)") (class "Default")
      (node (ref "ARDUINO_DUE2") (pin "43") (pinfunction "43_43") (pintype "bidirectional"))
    )
    (net (code "215") (name "unconnected-(ARDUINO_DUE2-Pad44)") (class "Default")
      (node (ref "ARDUINO_DUE2") (pin "44") (pinfunction "44_44") (pintype "bidirectional"))
    )
    (net (code "216") (name "unconnected-(ARDUINO_DUE2-Pad45)") (class "Default")
      (node (ref "ARDUINO_DUE2") (pin "45") (pinfunction "45_45") (pintype "bidirectional"))
    )
    (net (code "217") (name "unconnected-(ARDUINO_DUE2-Pad46)") (class "Default")
      (node (ref "ARDUINO_DUE2") (pin "46") (pinfunction "46_46") (pintype "bidirectional"))
    )
    (net (code "218") (name "unconnected-(ARDUINO_DUE2-Pad47)") (class "Default")
      (node (ref "ARDUINO_DUE2") (pin "47") (pinfunction "47_47") (pintype "bidirectional"))
    )
    (net (code "219") (name "unconnected-(ARDUINO_DUE2-Pad48)") (class "Default")
      (node (ref "ARDUINO_DUE2") (pin "48") (pinfunction "48_48") (pintype "bidirectional"))
    )
    (net (code "220") (name "unconnected-(ARDUINO_DUE2-Pad49)") (class "Default")
      (node (ref "ARDUINO_DUE2") (pin "49") (pinfunction "49_49") (pintype "bidirectional"))
    )
    (net (code "221") (name "unconnected-(ARDUINO_DUE2-Pad50)") (class "Default")
      (node (ref "ARDUINO_DUE2") (pin "50") (pinfunction "50_50") (pintype "bidirectional"))
    )
    (net (code "222") (name "unconnected-(ARDUINO_DUE2-Pad51)") (class "Default")
      (node (ref "ARDUINO_DUE2") (pin "51") (pinfunction "51_51") (pintype "bidirectional"))
    )
    (net (code "223") (name "unconnected-(ARDUINO_DUE2-Pad52)") (class "Default")
      (node (ref "ARDUINO_DUE2") (pin "52") (pinfunction "52_52") (pintype "bidirectional"))
    )
    (net (code "224") (name "unconnected-(ARDUINO_DUE2-Pad53)") (class "Default")
      (node (ref "ARDUINO_DUE2") (pin "53") (pinfunction "53_53") (pintype "bidirectional"))
    )
    (net (code "225") (name "unconnected-(ARDUINO_DUE2-PadAREF)") (class "Default")
      (node (ref "ARDUINO_DUE2") (pin "AREF") (pinfunction "AREF_AREF") (pintype "bidirectional"))
    )
    (net (code "226") (name "unconnected-(ARDUINO_DUE2-PadGND)") (class "Default")
      (node (ref "ARDUINO_DUE2") (pin "GND") (pinfunction "GND_GND") (pintype "bidirectional"))
    )
    (net (code "227") (name "unconnected-(ARDUINO_DUE2-PadIOREF)") (class "Default")
      (node (ref "ARDUINO_DUE2") (pin "IOREF") (pinfunction "IOREF_IOREF") (pintype "bidirectional"))
    )
    (net (code "228") (name "unconnected-(ARDUINO_DUE2-PadSCL1)") (class "Default")
      (node (ref "ARDUINO_DUE2") (pin "SCL1") (pinfunction "SCL1_SCL1") (pintype "bidirectional"))
    )
    (net (code "229") (name "unconnected-(ARDUINO_DUE2-PadSDA1)") (class "Default")
      (node (ref "ARDUINO_DUE2") (pin "SDA1") (pinfunction "SDA1_SDA1") (pintype "bidirectional"))
    )
    (net (code "230") (name "unconnected-(ARDUINO_DUE2-PadVIN)") (class "Default")
      (node (ref "ARDUINO_DUE2") (pin "VIN") (pinfunction "VIN_VIN") (pintype "bidirectional"))
    )
    (net (code "231") (name "unconnected-(ARDUINO_DUE2-RX0<0-Pad0)") (class "Default")
      (node (ref "ARDUINO_DUE2") (pin "0") (pinfunction "RX0<0_0") (pintype "bidirectional"))
    )
    (net (code "232") (name "unconnected-(ARDUINO_DUE2-RX2_17-Pad17)") (class "Default")
      (node (ref "ARDUINO_DUE2") (pin "17") (pinfunction "RX2_17_17") (pintype "bidirectional"))
    )
    (net (code "233") (name "unconnected-(ARDUINO_DUE2-RX3_15-Pad15)") (class "Default")
      (node (ref "ARDUINO_DUE2") (pin "15") (pinfunction "RX3_15_15") (pintype "bidirectional"))
    )
    (net (code "234") (name "unconnected-(ARDUINO_DUE2-SCL_21-Pad21)") (class "Default")
      (node (ref "ARDUINO_DUE2") (pin "21") (pinfunction "SCL_21_21") (pintype "bidirectional"))
    )
    (net (code "235") (name "unconnected-(ARDUINO_DUE2-SDA_20-Pad20)") (class "Default")
      (node (ref "ARDUINO_DUE2") (pin "20") (pinfunction "SDA_20_20") (pintype "bidirectional"))
    )
    (net (code "236") (name "unconnected-(ARDUINO_DUE2-TX0>1-Pad1)") (class "Default")
      (node (ref "ARDUINO_DUE2") (pin "1") (pinfunction "TX0>1_1") (pintype "bidirectional"))
    )
    (net (code "237") (name "unconnected-(ARDUINO_DUE2-TX2_16-Pad16)") (class "Default")
      (node (ref "ARDUINO_DUE2") (pin "16") (pinfunction "TX2_16_16") (pintype "bidirectional"))
    )
    (net (code "238") (name "unconnected-(ARDUINO_DUE2-TX3_14-Pad14)") (class "Default")
      (node (ref "ARDUINO_DUE2") (pin "14") (pinfunction "TX3_14_14") (pintype "bidirectional"))
    )
    (net (code "239") (name "unconnected-(S1A-O-Pad1)") (class "Default")
      (node (ref "S1") (pin "1") (pinfunction "O_1") (pintype "passive"))
    )
    (net (code "240") (name "unconnected-(S2A-O-Pad1)") (class "Default")
      (node (ref "S2") (pin "1") (pinfunction "O_1") (pintype "passive"))
    )
    (net (code "241") (name "unconnected-(S3-P1-Pad4)") (class "Default")
      (node (ref "S3") (pin "4") (pinfunction "P1_4") (pintype "passive"))
    )
    (net (code "242") (name "unconnected-(S3-S-Pad1)") (class "Default")
      (node (ref "S3") (pin "1") (pinfunction "S_1") (pintype "passive"))
    )
    (net (code "243") (name "unconnected-(S4-P1-Pad4)") (class "Default")
      (node (ref "S4") (pin "4") (pinfunction "P1_4") (pintype "passive"))
    )
    (net (code "244") (name "unconnected-(S4-S-Pad1)") (class "Default")
      (node (ref "S4") (pin "1") (pinfunction "S_1") (pintype "passive"))
    )
  )
)
